# LS1C300B_176A_Msystem.net
KiCad netlist of a schematic drawn in Altium Designer
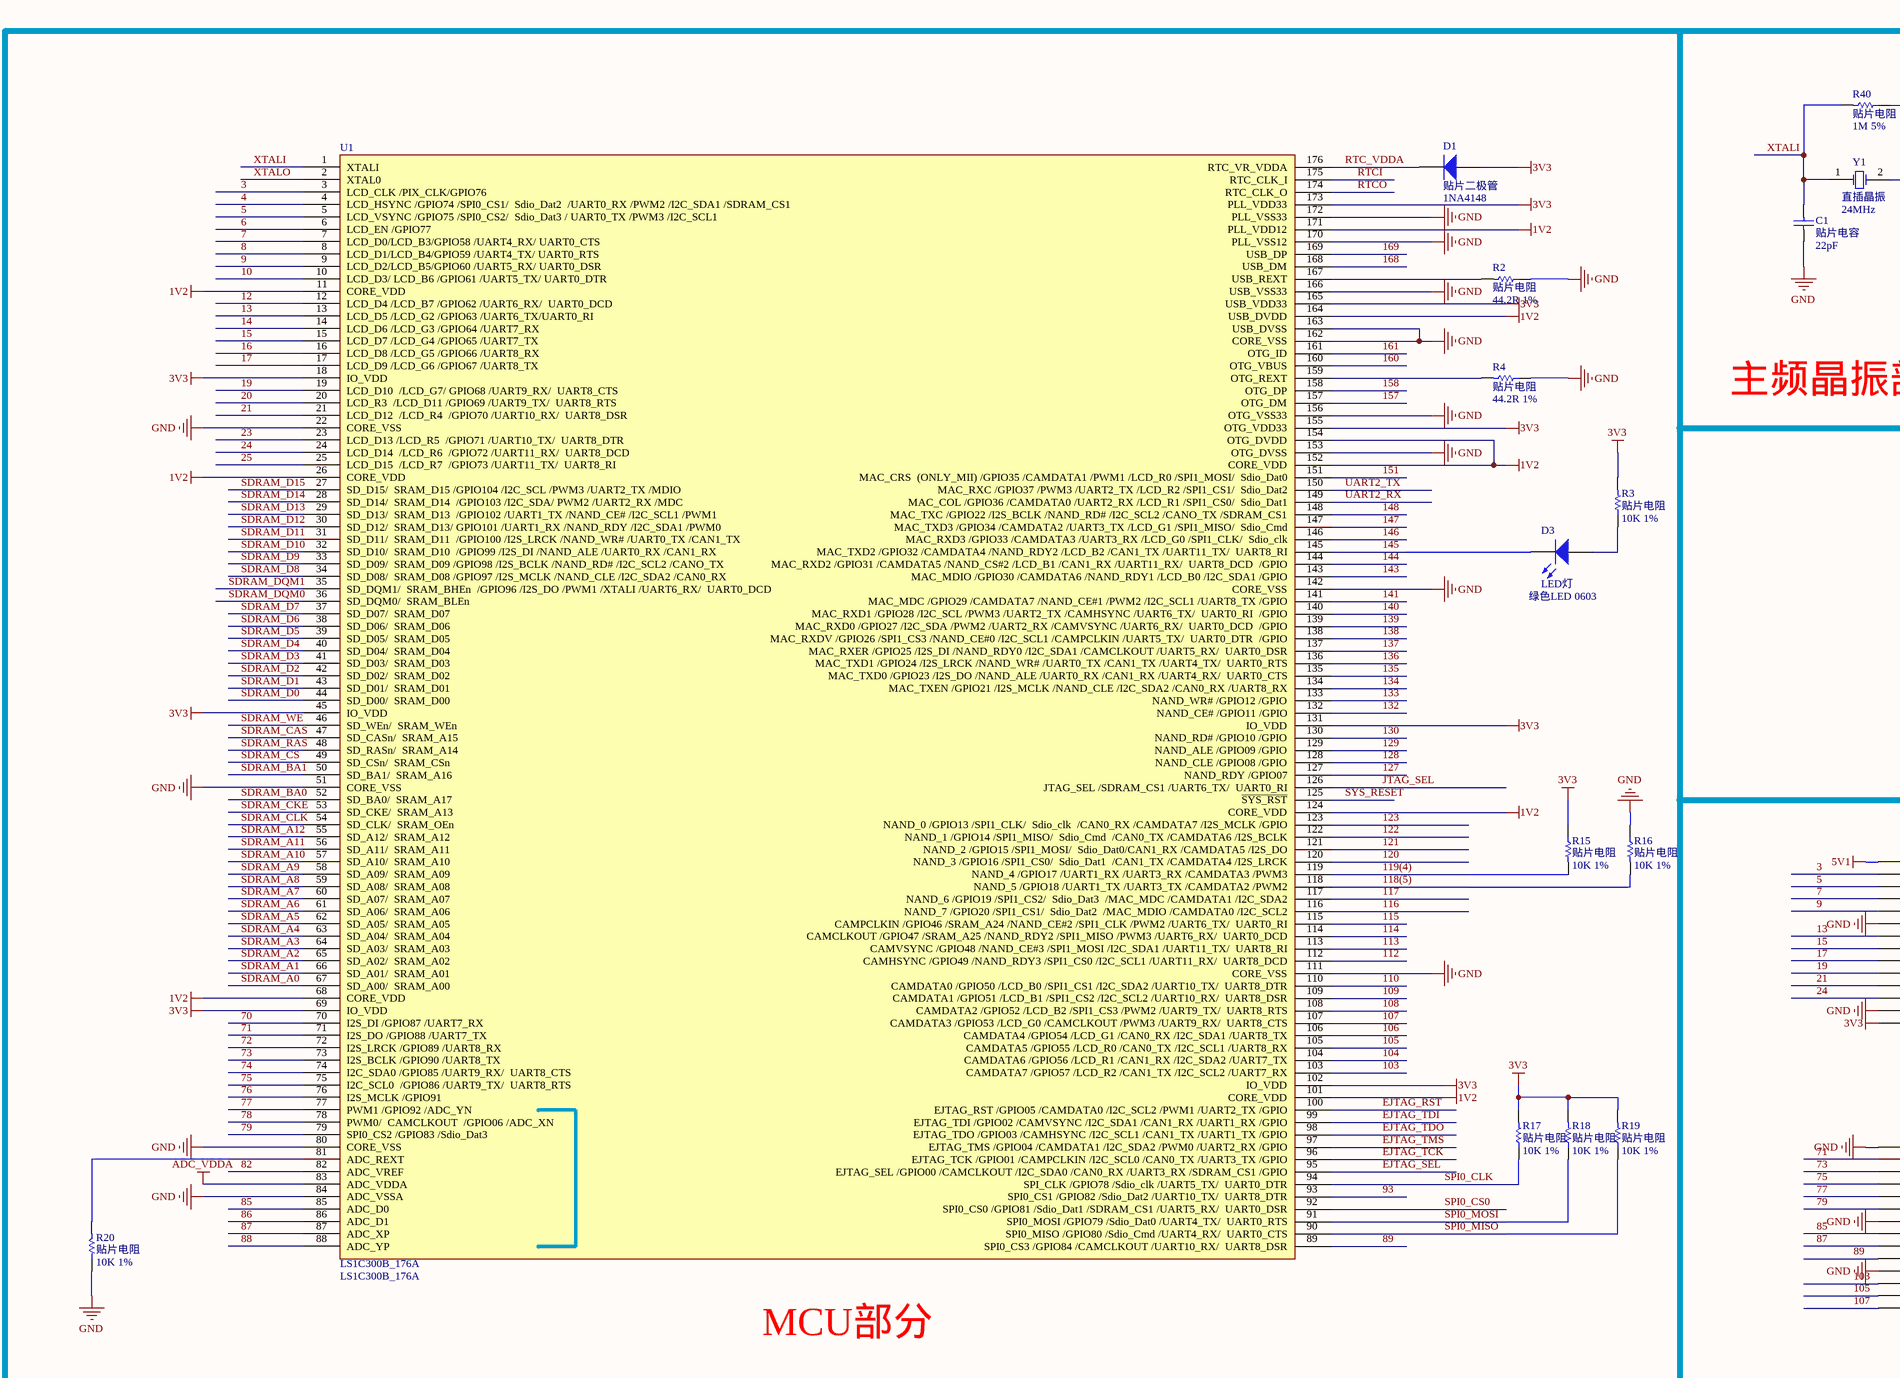
[diagram p0: LS1C300B_176A_Msystem.SchDoc, top left]
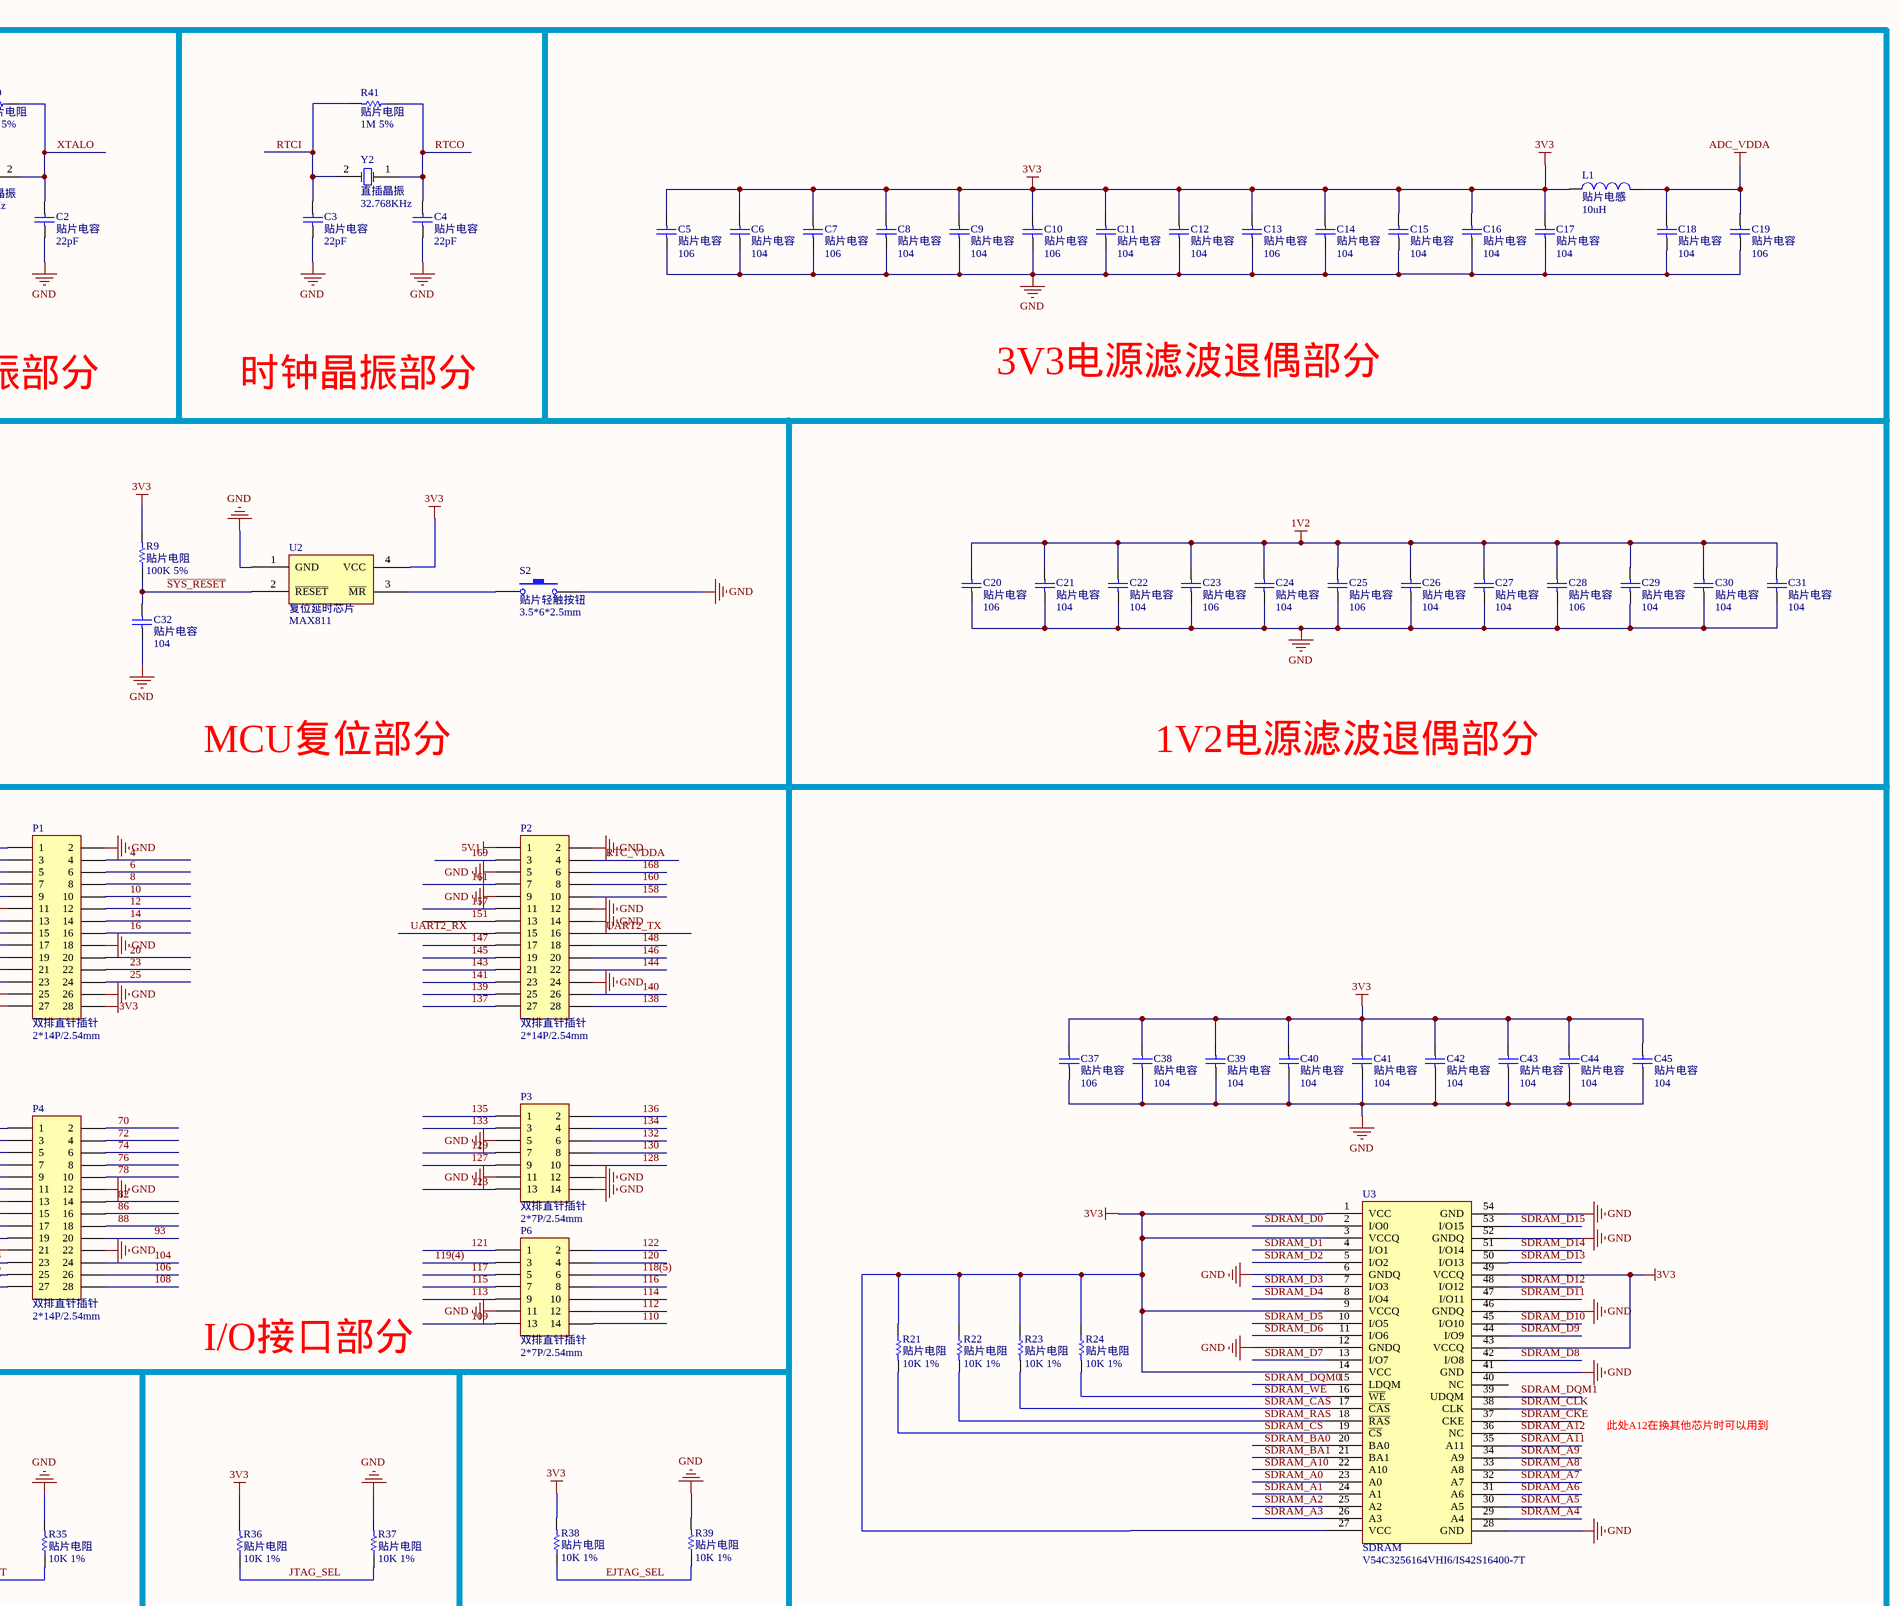
[diagram p1: LS1C300B_176A_Msystem.SchDoc, top right]
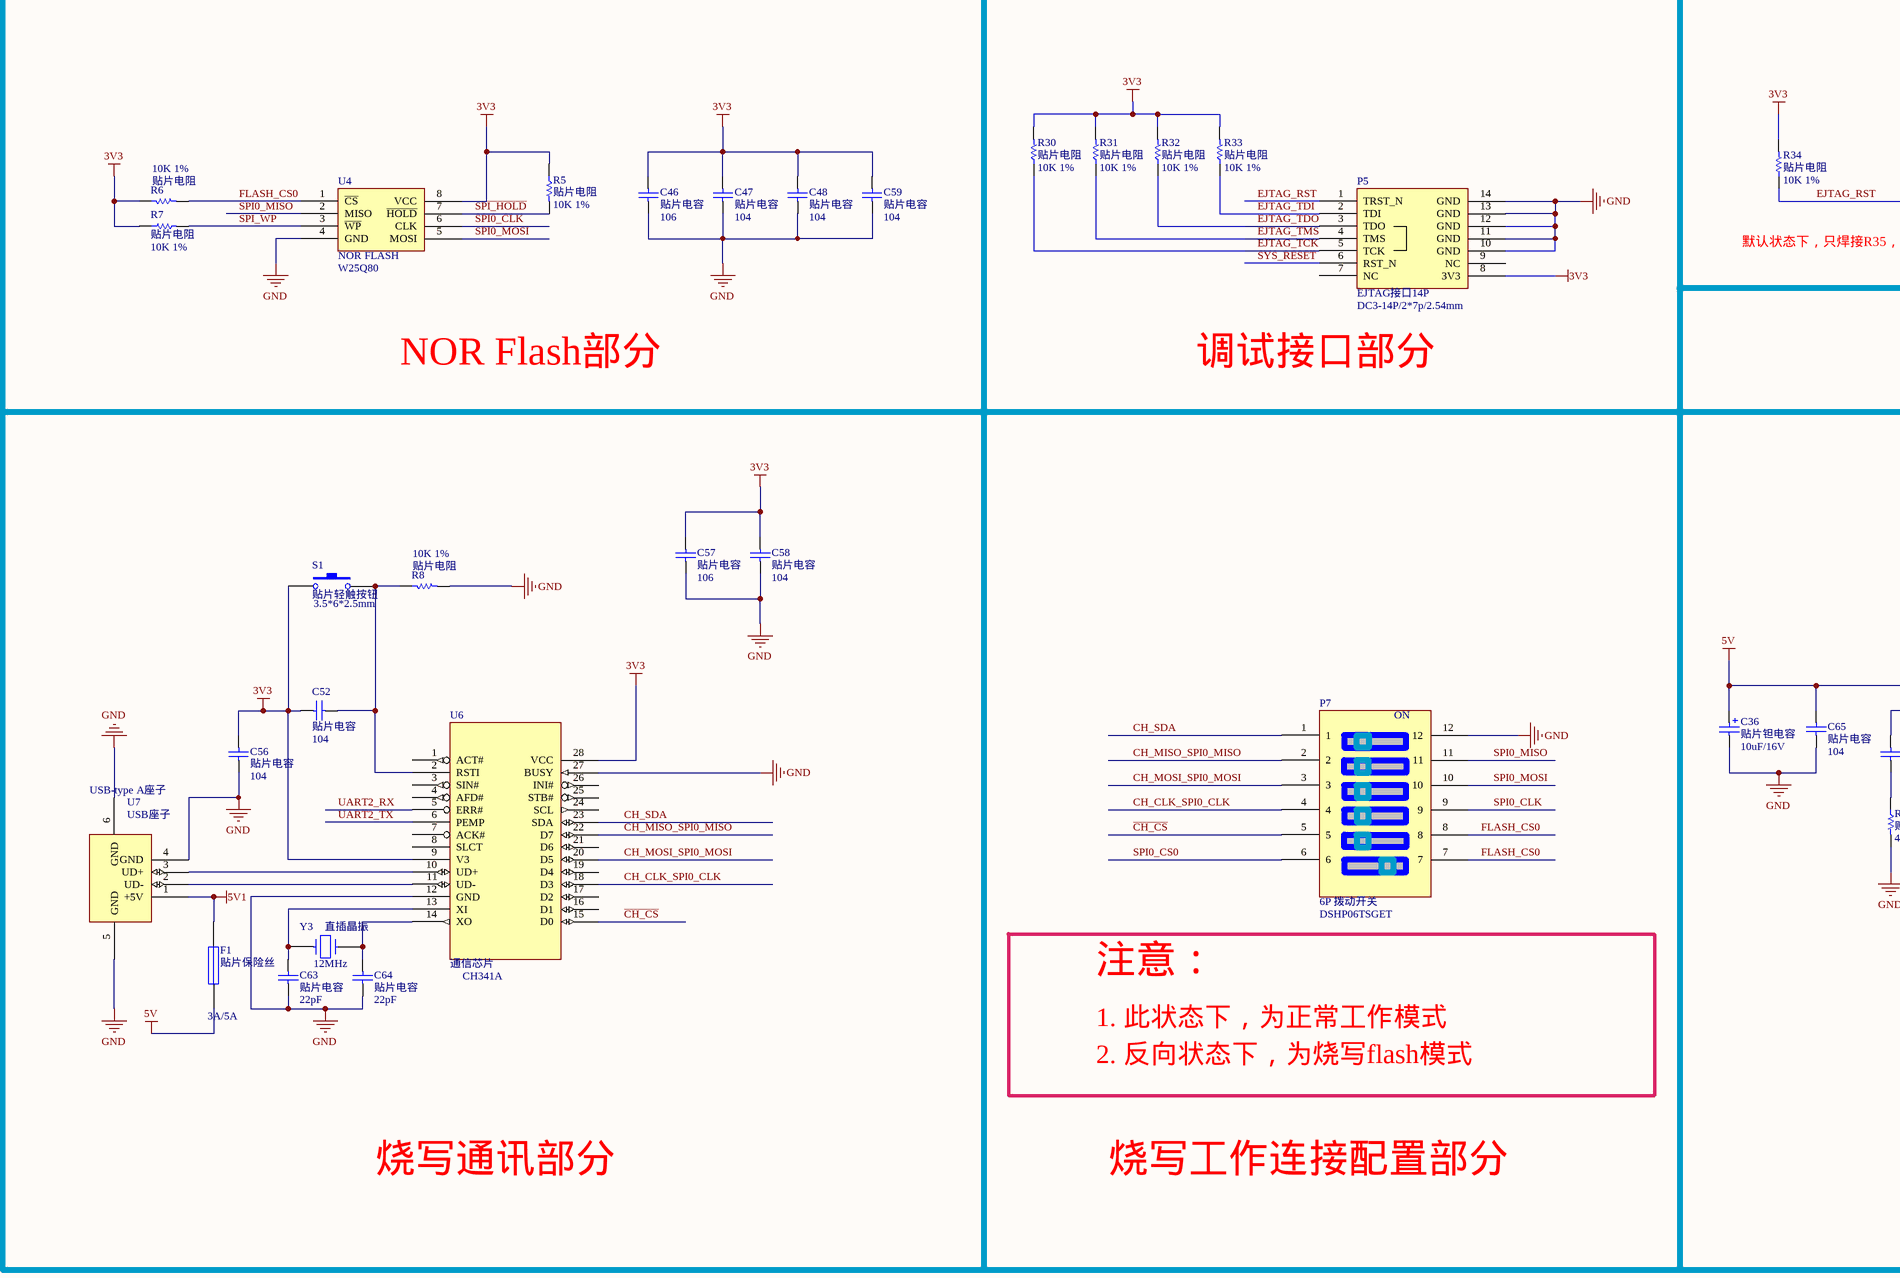
[diagram p2: LS1C300B_176A_Msystem.SchDoc, bottom left]
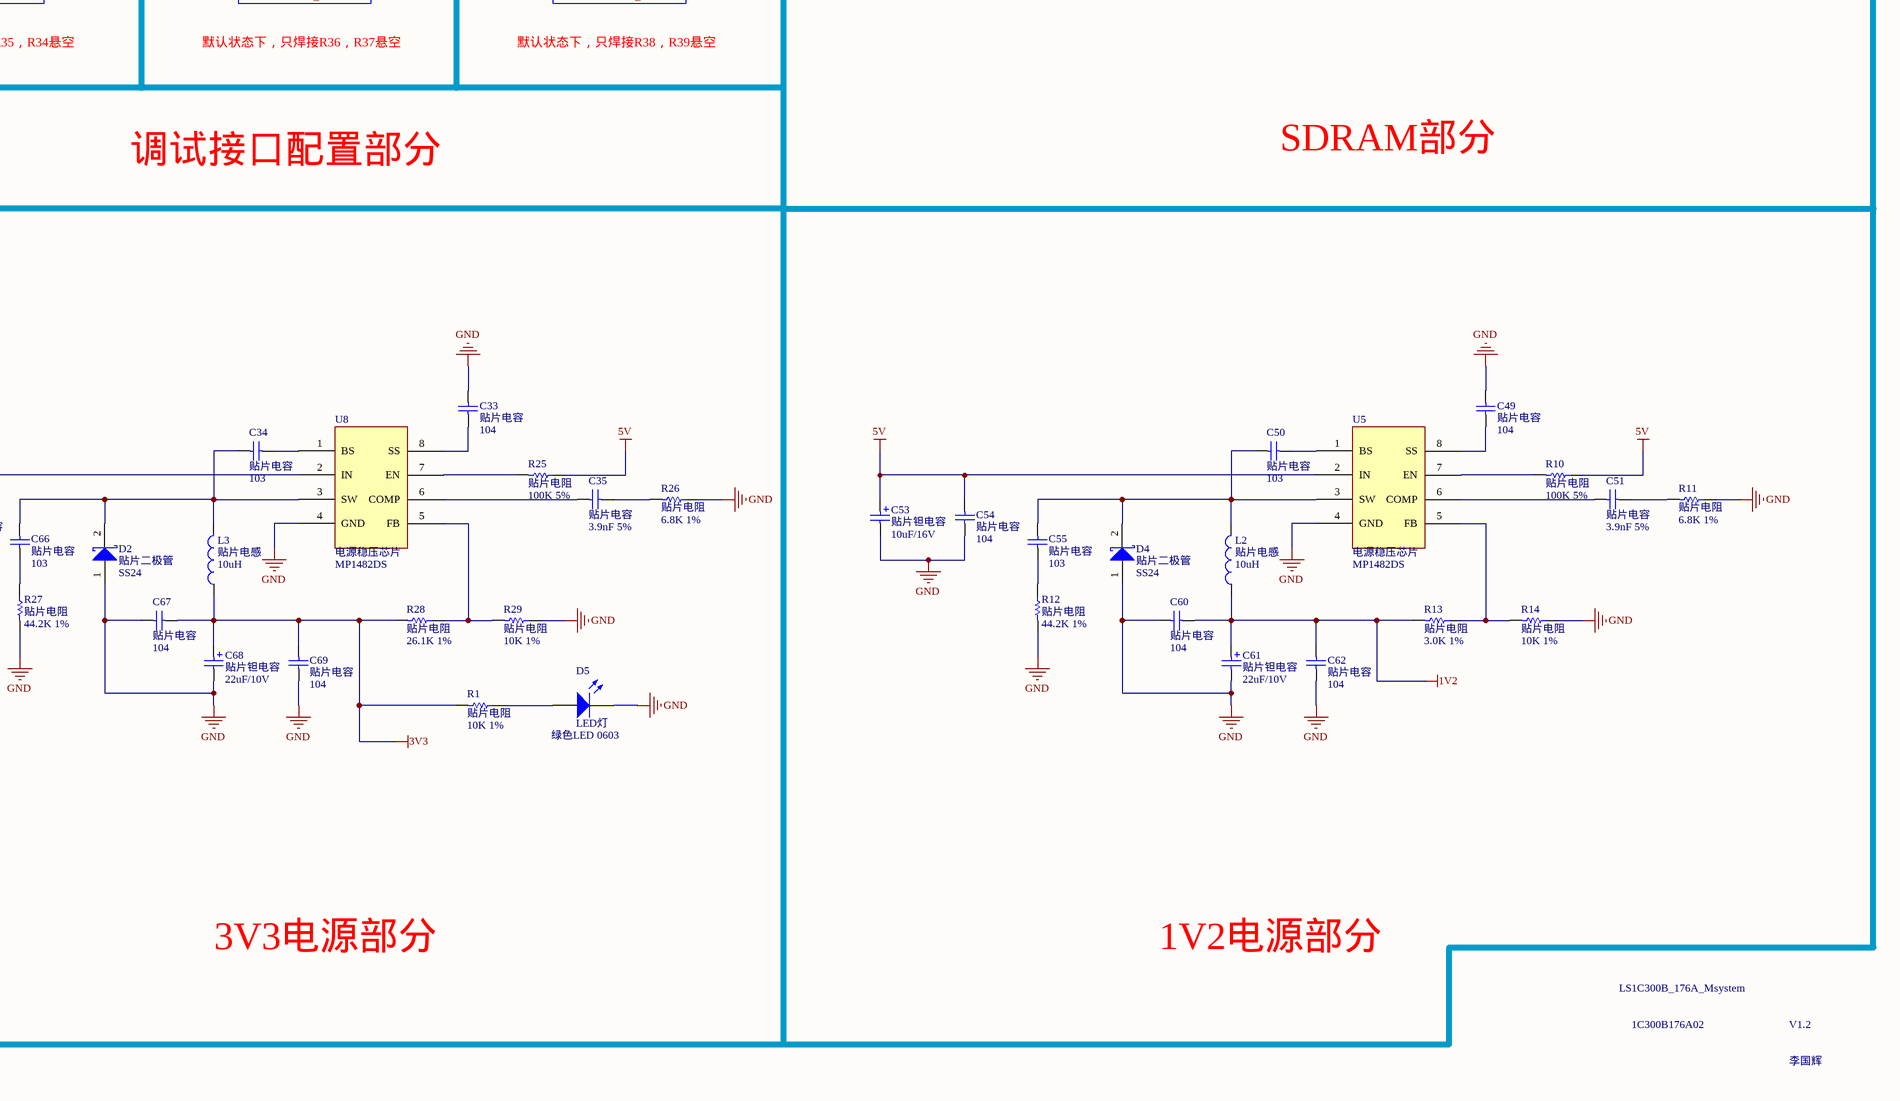
[diagram p3: LS1C300B_176A_Msystem.SchDoc, bottom right]

(export (version "E")
  (design (tool "Eeschema 10.0.6"))
  (components
    (comp (ref "C1")
      (value "贴片电容")
      (footprint "C0603")
      (description "Capacitor")
      (fields (field (name "ALTIUM_VALUE") "22pF") (field (name "PUBLISHER") "Altium Limited"))
      (libsource (lib "Miscellaneous Devices") (part "Cap"))
    )
    (comp (ref "C2")
      (value "贴片电容")
      (footprint "C0603")
      (description "Capacitor")
      (fields (field (name "ALTIUM_VALUE") "22pF") (field (name "PUBLISHER") "Altium Limited"))
      (libsource (lib "Miscellaneous Devices") (part "Cap"))
    )
    (comp (ref "C3")
      (value "贴片电容")
      (footprint "C0603")
      (description "Capacitor")
      (fields (field (name "ALTIUM_VALUE") "22pF") (field (name "PUBLISHER") "Altium Limited"))
      (libsource (lib "Miscellaneous Devices") (part "Cap"))
    )
    (comp (ref "C4")
      (value "贴片电容")
      (footprint "C0603")
      (description "Capacitor")
      (fields (field (name "ALTIUM_VALUE") "22pF") (field (name "PUBLISHER") "Altium Limited"))
      (libsource (lib "Miscellaneous Devices") (part "Cap"))
    )
    (comp (ref "C5")
      (value "贴片电容")
      (footprint "C0603")
      (description "Capacitor")
      (fields (field (name "ALTIUM_VALUE") "106") (field (name "PUBLISHER") "Altium Limited"))
      (libsource (lib "Miscellaneous Devices") (part "Cap"))
    )
    (comp (ref "C6")
      (value "贴片电容")
      (footprint "C0603")
      (description "Capacitor")
      (fields (field (name "ALTIUM_VALUE") "104") (field (name "PUBLISHER") "Altium Limited"))
      (libsource (lib "Miscellaneous Devices") (part "Cap"))
    )
    (comp (ref "C7")
      (value "贴片电容")
      (footprint "C0603")
      (description "Capacitor")
      (fields (field (name "ALTIUM_VALUE") "106") (field (name "PUBLISHER") "Altium Limited"))
      (libsource (lib "Miscellaneous Devices") (part "Cap"))
    )
    (comp (ref "C8")
      (value "贴片电容")
      (footprint "C0603")
      (description "Capacitor")
      (fields (field (name "ALTIUM_VALUE") "104") (field (name "PUBLISHER") "Altium Limited"))
      (libsource (lib "Miscellaneous Devices") (part "Cap"))
    )
    (comp (ref "C9")
      (value "贴片电容")
      (footprint "C0603")
      (description "Capacitor")
      (fields (field (name "ALTIUM_VALUE") "104") (field (name "PUBLISHER") "Altium Limited"))
      (libsource (lib "Miscellaneous Devices") (part "Cap"))
    )
    (comp (ref "C10")
      (value "贴片电容")
      (footprint "C0603")
      (description "Capacitor")
      (fields (field (name "ALTIUM_VALUE") "106") (field (name "PUBLISHER") "Altium Limited"))
      (libsource (lib "Miscellaneous Devices") (part "Cap"))
    )
    (comp (ref "C11")
      (value "贴片电容")
      (footprint "C0603")
      (description "Capacitor")
      (fields (field (name "ALTIUM_VALUE") "104") (field (name "PUBLISHER") "Altium Limited"))
      (libsource (lib "Miscellaneous Devices") (part "Cap"))
    )
    (comp (ref "C12")
      (value "贴片电容")
      (footprint "C0603")
      (description "Capacitor")
      (fields (field (name "ALTIUM_VALUE") "104") (field (name "PUBLISHER") "Altium Limited"))
      (libsource (lib "Miscellaneous Devices") (part "Cap"))
    )
    (comp (ref "C13")
      (value "贴片电容")
      (footprint "C0603")
      (description "Capacitor")
      (fields (field (name "ALTIUM_VALUE") "106") (field (name "PUBLISHER") "Altium Limited"))
      (libsource (lib "Miscellaneous Devices") (part "Cap"))
    )
    (comp (ref "C14")
      (value "贴片电容")
      (footprint "C0603")
      (description "Capacitor")
      (fields (field (name "ALTIUM_VALUE") "104") (field (name "PUBLISHER") "Altium Limited"))
      (libsource (lib "Miscellaneous Devices") (part "Cap"))
    )
    (comp (ref "C15")
      (value "贴片电容")
      (footprint "C0603")
      (description "Capacitor")
      (fields (field (name "ALTIUM_VALUE") "104") (field (name "PUBLISHER") "Altium Limited"))
      (libsource (lib "Miscellaneous Devices") (part "Cap"))
    )
    (comp (ref "C16")
      (value "贴片电容")
      (footprint "C0603")
      (description "Capacitor")
      (fields (field (name "ALTIUM_VALUE") "104") (field (name "PUBLISHER") "Altium Limited"))
      (libsource (lib "Miscellaneous Devices") (part "Cap"))
    )
    (comp (ref "C17")
      (value "贴片电容")
      (footprint "C0603")
      (description "Capacitor")
      (fields (field (name "ALTIUM_VALUE") "104") (field (name "PUBLISHER") "Altium Limited"))
      (libsource (lib "Miscellaneous Devices") (part "Cap"))
    )
    (comp (ref "C18")
      (value "贴片电容")
      (footprint "C0603")
      (description "Capacitor")
      (fields (field (name "ALTIUM_VALUE") "104") (field (name "PUBLISHER") "Altium Limited"))
      (libsource (lib "Miscellaneous Devices") (part "Cap"))
    )
    (comp (ref "C19")
      (value "贴片电容")
      (footprint "C0603")
      (description "Capacitor")
      (fields (field (name "ALTIUM_VALUE") "106") (field (name "PUBLISHER") "Altium Limited"))
      (libsource (lib "Miscellaneous Devices") (part "Cap"))
    )
    (comp (ref "C20")
      (value "贴片电容")
      (footprint "C0603")
      (description "Capacitor")
      (fields (field (name "ALTIUM_VALUE") "106") (field (name "PUBLISHER") "Altium Limited"))
      (libsource (lib "Miscellaneous Devices") (part "Cap"))
    )
    (comp (ref "C21")
      (value "贴片电容")
      (footprint "C0603")
      (description "Capacitor")
      (fields (field (name "ALTIUM_VALUE") "104") (field (name "PUBLISHER") "Altium Limited"))
      (libsource (lib "Miscellaneous Devices") (part "Cap"))
    )
    (comp (ref "C22")
      (value "贴片电容")
      (footprint "C0603")
      (description "Capacitor")
      (fields (field (name "ALTIUM_VALUE") "104") (field (name "PUBLISHER") "Altium Limited"))
      (libsource (lib "Miscellaneous Devices") (part "Cap"))
    )
    (comp (ref "C23")
      (value "贴片电容")
      (footprint "C0603")
      (description "Capacitor")
      (fields (field (name "ALTIUM_VALUE") "106") (field (name "PUBLISHER") "Altium Limited"))
      (libsource (lib "Miscellaneous Devices") (part "Cap"))
    )
    (comp (ref "C24")
      (value "贴片电容")
      (footprint "C0603")
      (description "Capacitor")
      (fields (field (name "ALTIUM_VALUE") "104") (field (name "PUBLISHER") "Altium Limited"))
      (libsource (lib "Miscellaneous Devices") (part "Cap"))
    )
    (comp (ref "C25")
      (value "贴片电容")
      (footprint "C0603")
      (description "Capacitor")
      (fields (field (name "ALTIUM_VALUE") "106") (field (name "PUBLISHER") "Altium Limited"))
      (libsource (lib "Miscellaneous Devices") (part "Cap"))
    )
    (comp (ref "C26")
      (value "贴片电容")
      (footprint "C0603")
      (description "Capacitor")
      (fields (field (name "ALTIUM_VALUE") "104") (field (name "PUBLISHER") "Altium Limited"))
      (libsource (lib "Miscellaneous Devices") (part "Cap"))
    )
    (comp (ref "C27")
      (value "贴片电容")
      (footprint "C0603")
      (description "Capacitor")
      (fields (field (name "ALTIUM_VALUE") "104") (field (name "PUBLISHER") "Altium Limited"))
      (libsource (lib "Miscellaneous Devices") (part "Cap"))
    )
    (comp (ref "C28")
      (value "贴片电容")
      (footprint "C0603")
      (description "Capacitor")
      (fields (field (name "ALTIUM_VALUE") "106") (field (name "PUBLISHER") "Altium Limited"))
      (libsource (lib "Miscellaneous Devices") (part "Cap"))
    )
    (comp (ref "C29")
      (value "贴片电容")
      (footprint "C0603")
      (description "Capacitor")
      (fields (field (name "ALTIUM_VALUE") "104") (field (name "PUBLISHER") "Altium Limited"))
      (libsource (lib "Miscellaneous Devices") (part "Cap"))
    )
    (comp (ref "C30")
      (value "贴片电容")
      (footprint "C0603")
      (description "Capacitor")
      (fields (field (name "ALTIUM_VALUE") "104") (field (name "PUBLISHER") "Altium Limited"))
      (libsource (lib "Miscellaneous Devices") (part "Cap"))
    )
    (comp (ref "C31")
      (value "贴片电容")
      (footprint "C0603")
      (description "Capacitor")
      (fields (field (name "ALTIUM_VALUE") "104") (field (name "PUBLISHER") "Altium Limited"))
      (libsource (lib "Miscellaneous Devices") (part "Cap"))
    )
    (comp (ref "C32")
      (value "贴片电容")
      (footprint "C0603")
      (description "Capacitor")
      (fields (field (name "ALTIUM_VALUE") "104") (field (name "PUBLISHER") "Altium Limited"))
      (libsource (lib "Miscellaneous Devices") (part "Cap"))
    )
    (comp (ref "C33")
      (value "贴片电容")
      (footprint "C0603")
      (description "Capacitor")
      (fields (field (name "ALTIUM_VALUE") "104") (field (name "PUBLISHER") "Altium Limited"))
      (libsource (lib "Miscellaneous Devices") (part "Cap"))
    )
    (comp (ref "C34")
      (value "贴片电容")
      (footprint "C0603")
      (description "Capacitor")
      (fields (field (name "ALTIUM_VALUE") "103") (field (name "PUBLISHER") "Altium Limited"))
      (libsource (lib "Miscellaneous Devices") (part "Cap"))
    )
    (comp (ref "C35")
      (value "贴片电容")
      (footprint "C0603")
      (description "Capacitor")
      (fields (field (name "ALTIUM_VALUE") "3.9nF 5%") (field (name "PUBLISHER") "Altium Limited"))
      (libsource (lib "Miscellaneous Devices") (part "Cap"))
    )
    (comp (ref "C36")
      (value "贴片钽电容")
      (footprint "P-C1206")
      (description "Polarized Capacitor (Axial)")
      (fields (field (name "ALTIUM_VALUE") "10uF/16V") (field (name "PUBLISHER") "Altium Limited"))
      (libsource (lib "Miscellaneous Devices") (part "Cap Pol2"))
    )
    (comp (ref "C37")
      (value "贴片电容")
      (footprint "C0603")
      (description "Capacitor")
      (fields (field (name "ALTIUM_VALUE") "106") (field (name "PUBLISHER") "Altium Limited"))
      (libsource (lib "Miscellaneous Devices") (part "Cap"))
    )
    (comp (ref "C38")
      (value "贴片电容")
      (footprint "C0603")
      (description "Capacitor")
      (fields (field (name "ALTIUM_VALUE") "104") (field (name "PUBLISHER") "Altium Limited"))
      (libsource (lib "Miscellaneous Devices") (part "Cap"))
    )
    (comp (ref "C39")
      (value "贴片电容")
      (footprint "C0603")
      (description "Capacitor")
      (fields (field (name "ALTIUM_VALUE") "104") (field (name "PUBLISHER") "Altium Limited"))
      (libsource (lib "Miscellaneous Devices") (part "Cap"))
    )
    (comp (ref "C40")
      (value "贴片电容")
      (footprint "C0603")
      (description "Capacitor")
      (fields (field (name "ALTIUM_VALUE") "104") (field (name "PUBLISHER") "Altium Limited"))
      (libsource (lib "Miscellaneous Devices") (part "Cap"))
    )
    (comp (ref "C41")
      (value "贴片电容")
      (footprint "C0603")
      (description "Capacitor")
      (fields (field (name "ALTIUM_VALUE") "104") (field (name "PUBLISHER") "Altium Limited"))
      (libsource (lib "Miscellaneous Devices") (part "Cap"))
    )
    (comp (ref "C42")
      (value "贴片电容")
      (footprint "C0603")
      (description "Capacitor")
      (fields (field (name "ALTIUM_VALUE") "104") (field (name "PUBLISHER") "Altium Limited"))
      (libsource (lib "Miscellaneous Devices") (part "Cap"))
    )
    (comp (ref "C43")
      (value "贴片电容")
      (footprint "C0603")
      (description "Capacitor")
      (fields (field (name "ALTIUM_VALUE") "104") (field (name "PUBLISHER") "Altium Limited"))
      (libsource (lib "Miscellaneous Devices") (part "Cap"))
    )
    (comp (ref "C44")
      (value "贴片电容")
      (footprint "C0603")
      (description "Capacitor")
      (fields (field (name "ALTIUM_VALUE") "104") (field (name "PUBLISHER") "Altium Limited"))
      (libsource (lib "Miscellaneous Devices") (part "Cap"))
    )
    (comp (ref "C45")
      (value "贴片电容")
      (footprint "C0603")
      (description "Capacitor")
      (fields (field (name "ALTIUM_VALUE") "104") (field (name "PUBLISHER") "Altium Limited"))
      (libsource (lib "Miscellaneous Devices") (part "Cap"))
    )
    (comp (ref "C46")
      (value "贴片电容")
      (footprint "C0603")
      (description "Capacitor")
      (fields (field (name "ALTIUM_VALUE") "106") (field (name "PUBLISHER") "Altium Limited"))
      (libsource (lib "Miscellaneous Devices") (part "Cap"))
    )
    (comp (ref "C47")
      (value "贴片电容")
      (footprint "C0603")
      (description "Capacitor")
      (fields (field (name "ALTIUM_VALUE") "104") (field (name "PUBLISHER") "Altium Limited"))
      (libsource (lib "Miscellaneous Devices") (part "Cap"))
    )
    (comp (ref "C48")
      (value "贴片电容")
      (footprint "C0603")
      (description "Capacitor")
      (fields (field (name "ALTIUM_VALUE") "104") (field (name "PUBLISHER") "Altium Limited"))
      (libsource (lib "Miscellaneous Devices") (part "Cap"))
    )
    (comp (ref "C49")
      (value "贴片电容")
      (footprint "C0603")
      (description "Capacitor")
      (fields (field (name "ALTIUM_VALUE") "104") (field (name "PUBLISHER") "Altium Limited"))
      (libsource (lib "Miscellaneous Devices") (part "Cap"))
    )
    (comp (ref "C50")
      (value "贴片电容")
      (footprint "C0603")
      (description "Capacitor")
      (fields (field (name "ALTIUM_VALUE") "103") (field (name "PUBLISHER") "Altium Limited"))
      (libsource (lib "Miscellaneous Devices") (part "Cap"))
    )
    (comp (ref "C51")
      (value "贴片电容")
      (footprint "C0603")
      (description "Capacitor")
      (fields (field (name "ALTIUM_VALUE") "3.9nF 5%") (field (name "PUBLISHER") "Altium Limited"))
      (libsource (lib "Miscellaneous Devices") (part "Cap"))
    )
    (comp (ref "C52")
      (value "贴片电容")
      (footprint "C0603")
      (description "Capacitor")
      (fields (field (name "ALTIUM_VALUE") "104") (field (name "PUBLISHER") "Altium Limited"))
      (libsource (lib "Miscellaneous Devices") (part "Cap"))
    )
    (comp (ref "C53")
      (value "贴片钽电容")
      (footprint "P-C1206")
      (description "Polarized Capacitor (Axial)")
      (fields (field (name "ALTIUM_VALUE") "10uF/16V") (field (name "PUBLISHER") "Altium Limited"))
      (libsource (lib "Miscellaneous Devices") (part "Cap Pol2"))
    )
    (comp (ref "C54")
      (value "贴片电容")
      (footprint "C0603")
      (description "Capacitor")
      (fields (field (name "ALTIUM_VALUE") "104") (field (name "PUBLISHER") "Altium Limited"))
      (libsource (lib "Miscellaneous Devices") (part "Cap"))
    )
    (comp (ref "C55")
      (value "贴片电容")
      (footprint "C0603")
      (description "Capacitor")
      (fields (field (name "ALTIUM_VALUE") "103") (field (name "PUBLISHER") "Altium Limited"))
      (libsource (lib "Miscellaneous Devices") (part "Cap"))
    )
    (comp (ref "C56")
      (value "贴片电容")
      (footprint "C0603")
      (description "Capacitor")
      (fields (field (name "ALTIUM_VALUE") "104") (field (name "PUBLISHER") "Altium Limited"))
      (libsource (lib "Miscellaneous Devices") (part "Cap"))
    )
    (comp (ref "C57")
      (value "贴片电容")
      (footprint "C0603")
      (description "Capacitor")
      (fields (field (name "ALTIUM_VALUE") "106") (field (name "PUBLISHER") "Altium Limited"))
      (libsource (lib "Miscellaneous Devices") (part "Cap"))
    )
    (comp (ref "C58")
      (value "贴片电容")
      (footprint "C0603")
      (description "Capacitor")
      (fields (field (name "ALTIUM_VALUE") "104") (field (name "PUBLISHER") "Altium Limited"))
      (libsource (lib "Miscellaneous Devices") (part "Cap"))
    )
    (comp (ref "C59")
      (value "贴片电容")
      (footprint "C0603")
      (description "Capacitor")
      (fields (field (name "ALTIUM_VALUE") "104") (field (name "PUBLISHER") "Altium Limited"))
      (libsource (lib "Miscellaneous Devices") (part "Cap"))
    )
    (comp (ref "C60")
      (value "贴片电容")
      (footprint "C0603")
      (description "Capacitor")
      (fields (field (name "ALTIUM_VALUE") "104") (field (name "PUBLISHER") "Altium Limited"))
      (libsource (lib "Miscellaneous Devices") (part "Cap"))
    )
    (comp (ref "C61")
      (value "贴片钽电容")
      (footprint "P-C1206")
      (description "Polarized Capacitor (Axial)")
      (fields (field (name "ALTIUM_VALUE") "22uF/10V") (field (name "PUBLISHER") "Altium Limited"))
      (libsource (lib "Miscellaneous Devices") (part "Cap Pol2"))
    )
    (comp (ref "C62")
      (value "贴片电容")
      (footprint "C0603")
      (description "Capacitor")
      (fields (field (name "ALTIUM_VALUE") "104") (field (name "PUBLISHER") "Altium Limited"))
      (libsource (lib "Miscellaneous Devices") (part "Cap"))
    )
    (comp (ref "C63")
      (value "贴片电容")
      (footprint "C0603")
      (description "Capacitor")
      (fields (field (name "ALTIUM_VALUE") "22pF") (field (name "PUBLISHER") "Altium Limited"))
      (libsource (lib "Miscellaneous Devices") (part "Cap"))
    )
    (comp (ref "C64")
      (value "贴片电容")
      (footprint "C0603")
      (description "Capacitor")
      (fields (field (name "ALTIUM_VALUE") "22pF") (field (name "PUBLISHER") "Altium Limited"))
      (libsource (lib "Miscellaneous Devices") (part "Cap"))
    )
    (comp (ref "C65")
      (value "贴片电容")
      (footprint "C0603")
      (description "Capacitor")
      (fields (field (name "ALTIUM_VALUE") "104") (field (name "PUBLISHER") "Altium Limited"))
      (libsource (lib "Miscellaneous Devices") (part "Cap"))
    )
    (comp (ref "C66")
      (value "贴片电容")
      (footprint "C0603")
      (description "Capacitor")
      (fields (field (name "ALTIUM_VALUE") "103") (field (name "PUBLISHER") "Altium Limited"))
      (libsource (lib "Miscellaneous Devices") (part "Cap"))
    )
    (comp (ref "C67")
      (value "贴片电容")
      (footprint "C0603")
      (description "Capacitor")
      (fields (field (name "ALTIUM_VALUE") "104") (field (name "PUBLISHER") "Altium Limited"))
      (libsource (lib "Miscellaneous Devices") (part "Cap"))
    )
    (comp (ref "C68")
      (value "贴片钽电容")
      (footprint "P-C1206")
      (description "Polarized Capacitor (Axial)")
      (fields (field (name "ALTIUM_VALUE") "22uF/10V") (field (name "PUBLISHER") "Altium Limited"))
      (libsource (lib "Miscellaneous Devices") (part "Cap Pol2"))
    )
    (comp (ref "C69")
      (value "贴片电容")
      (footprint "C0603")
      (description "Capacitor")
      (fields (field (name "ALTIUM_VALUE") "104") (field (name "PUBLISHER") "Altium Limited"))
      (libsource (lib "Miscellaneous Devices") (part "Cap"))
    )
    (comp (ref "D1")
      (value "贴片二极管")
      (footprint "LL-34")
      (description "Default Diode")
      (fields (field (name "ALTIUM_VALUE") "1NA4148") (field (name "PUBLISHER") "Altium Limited"))
      (libsource (lib "Miscellaneous Devices") (part "Diode"))
    )
    (comp (ref "D2")
      (value "贴片二极管")
      (footprint "DO-214AC")
      (fields (field (name "ALTIUM_VALUE") "SS24"))
      (libsource (lib "LGHLIB") (part "1N47xx"))
    )
    (comp (ref "D3")
      (value "LED灯")
      (footprint "LED-0603")
      (description "Typical INFRARED GaAs LED")
      (fields (field (name "ALTIUM_VALUE") "绿色LED 0603") (field (name "PUBLISHER") "Altium Limited"))
      (libsource (lib "Miscellaneous Devices") (part "LED0"))
    )
    (comp (ref "D4")
      (value "贴片二极管")
      (footprint "DO-214AC")
      (fields (field (name "ALTIUM_VALUE") "SS24"))
      (libsource (lib "LGHLIB") (part "1N47xx"))
    )
    (comp (ref "D5")
      (value "LED灯")
      (footprint "LED-0603")
      (description "Typical INFRARED GaAs LED")
      (fields (field (name "ALTIUM_VALUE") "绿色LED 0603") (field (name "PUBLISHER") "Altium Limited"))
      (libsource (lib "Miscellaneous Devices") (part "LED0"))
    )
    (comp (ref "F1")
      (value "贴片保险丝")
      (footprint "R1206")
      (description "Fuse")
      (fields (field (name "ALTIUM_VALUE") "3A/5A") (field (name "PUBLISHER") "Altium Limited"))
      (libsource (lib "Miscellaneous Devices") (part "Fuse 1"))
    )
    (comp (ref "L1")
      (value "贴片电感")
      (footprint "L0603")
      (description "Inductor")
      (fields (field (name "ALTIUM_VALUE") "10uH") (field (name "PUBLISHER") "Altium Limited"))
      (libsource (lib "Miscellaneous Devices") (part "Inductor"))
    )
    (comp (ref "L2")
      (value "贴片电感")
      (footprint "L0603")
      (description "Inductor")
      (fields (field (name "ALTIUM_VALUE") "10uH") (field (name "PUBLISHER") "Altium Limited"))
      (libsource (lib "Miscellaneous Devices") (part "Inductor"))
    )
    (comp (ref "L3")
      (value "贴片电感")
      (footprint "L0603")
      (description "Inductor")
      (fields (field (name "ALTIUM_VALUE") "10uH") (field (name "PUBLISHER") "Altium Limited"))
      (libsource (lib "Miscellaneous Devices") (part "Inductor"))
    )
    (comp (ref "P1")
      (value "双排直针插针")
      (footprint "HDR2X14")
      (description "Header, 14-Pin, Dual row")
      (fields (field (name "ALTIUM_VALUE") "2*14P/2.54mm") (field (name "PUBLISHER") "Altium Limited"))
      (libsource (lib "Miscellaneous Connectors") (part "MHDR2X14"))
    )
    (comp (ref "P2")
      (value "双排直针插针")
      (footprint "HDR2X14")
      (description "Header, 14-Pin, Dual row")
      (fields (field (name "ALTIUM_VALUE") "2*14P/2.54mm") (field (name "PUBLISHER") "Altium Limited"))
      (libsource (lib "Miscellaneous Connectors") (part "MHDR2X14"))
    )
    (comp (ref "P3")
      (value "双排直针插针")
      (footprint "HDR2X7")
      (description "Header, 7-Pin, Dual row")
      (fields (field (name "ALTIUM_VALUE") "2*7P/2.54mm") (field (name "PUBLISHER") "Altium Limited"))
      (libsource (lib "Miscellaneous Connectors") (part "MHDR2X7"))
    )
    (comp (ref "P4")
      (value "双排直针插针")
      (footprint "HDR2X14")
      (description "Header, 14-Pin, Dual row")
      (fields (field (name "ALTIUM_VALUE") "2*14P/2.54mm") (field (name "PUBLISHER") "Altium Limited"))
      (libsource (lib "Miscellaneous Connectors") (part "MHDR2X14"))
    )
    (comp (ref "P5")
      (value "EJTAG接口14P")
      (footprint "DC3-14P")
      (fields (field (name "ALTIUM_VALUE") "DC3-14P/2*7p/2.54mm"))
      (libsource (lib "LGHLIB") (part "EJTAG-14P"))
    )
    (comp (ref "P6")
      (value "双排直针插针")
      (footprint "HDR2X7")
      (description "Header, 7-Pin, Dual row")
      (fields (field (name "ALTIUM_VALUE") "2*7P/2.54mm") (field (name "PUBLISHER") "Altium Limited"))
      (libsource (lib "Miscellaneous Connectors") (part "MHDR2X7"))
    )
    (comp (ref "P7")
      (value "6P 拨动开关")
      (footprint "DSHP06")
      (description "台湾KE 公司  DSHP06TSGET")
      (fields (field (name "ALTIUM_VALUE") "DSHP06TSGET"))
      (libsource (lib "LGHLIB") (part "DSHP06TSGET"))
    )
    (comp (ref "R1")
      (value "贴片电阻")
      (footprint "R0603")
      (description "Resistor")
      (fields (field (name "ALTIUM_VALUE") "10K 1%") (field (name "PUBLISHER") "Altium Limited"))
      (libsource (lib "Miscellaneous Devices") (part "Res1"))
    )
    (comp (ref "R2")
      (value "贴片电阻")
      (footprint "R0603")
      (description "Resistor")
      (fields (field (name "ALTIUM_VALUE") "44.2R 1%") (field (name "PUBLISHER") "Altium Limited"))
      (libsource (lib "Miscellaneous Devices") (part "Res1"))
    )
    (comp (ref "R3")
      (value "贴片电阻")
      (footprint "R0603")
      (description "Resistor")
      (fields (field (name "ALTIUM_VALUE") "10K 1%") (field (name "PUBLISHER") "Altium Limited"))
      (libsource (lib "Miscellaneous Devices") (part "Res1"))
    )
    (comp (ref "R4")
      (value "贴片电阻")
      (footprint "R0603")
      (description "Resistor")
      (fields (field (name "ALTIUM_VALUE") "44.2R 1%") (field (name "PUBLISHER") "Altium Limited"))
      (libsource (lib "Miscellaneous Devices") (part "Res1"))
    )
    (comp (ref "R5")
      (value "贴片电阻")
      (footprint "R0603")
      (description "Resistor")
      (fields (field (name "ALTIUM_VALUE") "10K 1%") (field (name "PUBLISHER") "Altium Limited"))
      (libsource (lib "Miscellaneous Devices") (part "Res1"))
    )
    (comp (ref "R6")
      (value "贴片电阻")
      (footprint "R0603")
      (description "Resistor")
      (fields (field (name "ALTIUM_VALUE") "10K 1%") (field (name "PUBLISHER") "Altium Limited"))
      (libsource (lib "Miscellaneous Devices") (part "Res1"))
    )
    (comp (ref "R7")
      (value "贴片电阻")
      (footprint "R0603")
      (description "Resistor")
      (fields (field (name "ALTIUM_VALUE") "10K 1%") (field (name "PUBLISHER") "Altium Limited"))
      (libsource (lib "Miscellaneous Devices") (part "Res1"))
    )
    (comp (ref "R8")
      (value "贴片电阻")
      (footprint "R0603")
      (description "Resistor")
      (fields (field (name "ALTIUM_VALUE") "10K 1%") (field (name "PUBLISHER") "Altium Limited"))
      (libsource (lib "Miscellaneous Devices") (part "Res1"))
    )
    (comp (ref "R9")
      (value "贴片电阻")
      (footprint "R0603")
      (description "Resistor")
      (fields (field (name "ALTIUM_VALUE") "100K 5%") (field (name "PUBLISHER") "Altium Limited"))
      (libsource (lib "Miscellaneous Devices") (part "Res1"))
    )
    (comp (ref "R10")
      (value "贴片电阻")
      (footprint "R0603")
      (description "Resistor")
      (fields (field (name "ALTIUM_VALUE") "100K 5%") (field (name "PUBLISHER") "Altium Limited"))
      (libsource (lib "Miscellaneous Devices") (part "Res1"))
    )
    (comp (ref "R11")
      (value "贴片电阻")
      (footprint "R0603")
      (description "Resistor")
      (fields (field (name "ALTIUM_VALUE") "6.8K 1%") (field (name "PUBLISHER") "Altium Limited"))
      (libsource (lib "Miscellaneous Devices") (part "Res1"))
    )
    (comp (ref "R12")
      (value "贴片电阻")
      (footprint "R0603")
      (description "Resistor")
      (fields (field (name "ALTIUM_VALUE") "44.2K 1%") (field (name "PUBLISHER") "Altium Limited"))
      (libsource (lib "Miscellaneous Devices") (part "Res1"))
    )
    (comp (ref "R13")
      (value "贴片电阻")
      (footprint "R0603")
      (description "Resistor")
      (fields (field (name "ALTIUM_VALUE") "3.0K 1%") (field (name "PUBLISHER") "Altium Limited"))
      (libsource (lib "Miscellaneous Devices") (part "Res1"))
    )
    (comp (ref "R14")
      (value "贴片电阻")
      (footprint "R0603")
      (description "Resistor")
      (fields (field (name "ALTIUM_VALUE") "10K 1%") (field (name "PUBLISHER") "Altium Limited"))
      (libsource (lib "Miscellaneous Devices") (part "Res1"))
    )
    (comp (ref "R15")
      (value "贴片电阻")
      (footprint "R0603")
      (description "Resistor")
      (fields (field (name "ALTIUM_VALUE") "10K 1%") (field (name "PUBLISHER") "Altium Limited"))
      (libsource (lib "Miscellaneous Devices") (part "Res1"))
    )
    (comp (ref "R16")
      (value "贴片电阻")
      (footprint "R0603")
      (description "Resistor")
      (fields (field (name "ALTIUM_VALUE") "10K 1%") (field (name "PUBLISHER") "Altium Limited"))
      (libsource (lib "Miscellaneous Devices") (part "Res1"))
    )
    (comp (ref "R17")
      (value "贴片电阻")
      (footprint "R0603")
      (description "Resistor")
      (fields (field (name "ALTIUM_VALUE") "10K 1%") (field (name "PUBLISHER") "Altium Limited"))
      (libsource (lib "Miscellaneous Devices") (part "Res1"))
    )
    (comp (ref "R18")
      (value "贴片电阻")
      (footprint "R0603")
      (description "Resistor")
      (fields (field (name "ALTIUM_VALUE") "10K 1%") (field (name "PUBLISHER") "Altium Limited"))
      (libsource (lib "Miscellaneous Devices") (part "Res1"))
    )
    (comp (ref "R19")
      (value "贴片电阻")
      (footprint "R0603")
      (description "Resistor")
      (fields (field (name "ALTIUM_VALUE") "10K 1%") (field (name "PUBLISHER") "Altium Limited"))
      (libsource (lib "Miscellaneous Devices") (part "Res1"))
    )
    (comp (ref "R20")
      (value "贴片电阻")
      (footprint "R0603")
      (description "Resistor")
      (fields (field (name "ALTIUM_VALUE") "10K 1%") (field (name "PUBLISHER") "Altium Limited"))
      (libsource (lib "Miscellaneous Devices") (part "Res1"))
    )
    (comp (ref "R21")
      (value "贴片电阻")
      (footprint "R0603")
      (description "Resistor")
      (fields (field (name "ALTIUM_VALUE") "10K 1%") (field (name "PUBLISHER") "Altium Limited"))
      (libsource (lib "Miscellaneous Devices") (part "Res1"))
    )
    (comp (ref "R22")
      (value "贴片电阻")
      (footprint "R0603")
      (description "Resistor")
      (fields (field (name "ALTIUM_VALUE") "10K 1%") (field (name "PUBLISHER") "Altium Limited"))
      (libsource (lib "Miscellaneous Devices") (part "Res1"))
    )
    (comp (ref "R23")
      (value "贴片电阻")
      (footprint "R0603")
      (description "Resistor")
      (fields (field (name "ALTIUM_VALUE") "10K 1%") (field (name "PUBLISHER") "Altium Limited"))
      (libsource (lib "Miscellaneous Devices") (part "Res1"))
    )
    (comp (ref "R24")
      (value "贴片电阻")
      (footprint "R0603")
      (description "Resistor")
      (fields (field (name "ALTIUM_VALUE") "10K 1%") (field (name "PUBLISHER") "Altium Limited"))
      (libsource (lib "Miscellaneous Devices") (part "Res1"))
    )
    (comp (ref "R25")
      (value "贴片电阻")
      (footprint "R0603")
      (description "Resistor")
      (fields (field (name "ALTIUM_VALUE") "100K 5%") (field (name "PUBLISHER") "Altium Limited"))
      (libsource (lib "Miscellaneous Devices") (part "Res1"))
    )
    (comp (ref "R26")
      (value "贴片电阻")
      (footprint "R0603")
      (description "Resistor")
      (fields (field (name "ALTIUM_VALUE") "6.8K 1%") (field (name "PUBLISHER") "Altium Limited"))
      (libsource (lib "Miscellaneous Devices") (part "Res1"))
    )
    (comp (ref "R27")
      (value "贴片电阻")
      (footprint "R0603")
      (description "Resistor")
      (fields (field (name "ALTIUM_VALUE") "44.2K 1%") (field (name "PUBLISHER") "Altium Limited"))
      (libsource (lib "Miscellaneous Devices") (part "Res1"))
    )
    (comp (ref "R28")
      (value "贴片电阻")
      (footprint "R0603")
      (description "Resistor")
      (fields (field (name "ALTIUM_VALUE") "26.1K 1%") (field (name "PUBLISHER") "Altium Limited"))
      (libsource (lib "Miscellaneous Devices") (part "Res1"))
    )
    (comp (ref "R29")
      (value "贴片电阻")
      (footprint "R0603")
      (description "Resistor")
      (fields (field (name "ALTIUM_VALUE") "10K 1%") (field (name "PUBLISHER") "Altium Limited"))
      (libsource (lib "Miscellaneous Devices") (part "Res1"))
    )
    (comp (ref "R30")
      (value "贴片电阻")
      (footprint "R0603")
      (description "Resistor")
      (fields (field (name "ALTIUM_VALUE") "10K 1%") (field (name "PUBLISHER") "Altium Limited"))
      (libsource (lib "Miscellaneous Devices") (part "Res1"))
    )
    (comp (ref "R31")
      (value "贴片电阻")
      (footprint "R0603")
      (description "Resistor")
      (fields (field (name "ALTIUM_VALUE") "10K 1%") (field (name "PUBLISHER") "Altium Limited"))
      (libsource (lib "Miscellaneous Devices") (part "Res1"))
    )
    (comp (ref "R32")
      (value "贴片电阻")
      (footprint "R0603")
      (description "Resistor")
      (fields (field (name "ALTIUM_VALUE") "10K 1%") (field (name "PUBLISHER") "Altium Limited"))
      (libsource (lib "Miscellaneous Devices") (part "Res1"))
    )
    (comp (ref "R33")
      (value "贴片电阻")
      (footprint "R0603")
      (description "Resistor")
      (fields (field (name "ALTIUM_VALUE") "10K 1%") (field (name "PUBLISHER") "Altium Limited"))
      (libsource (lib "Miscellaneous Devices") (part "Res1"))
    )
    (comp (ref "R34")
      (value "贴片电阻")
      (footprint "R0603")
      (description "Resistor")
      (fields (field (name "ALTIUM_VALUE") "10K 1%") (field (name "PUBLISHER") "Altium Limited"))
      (libsource (lib "Miscellaneous Devices") (part "Res1"))
    )
    (comp (ref "R35")
      (value "贴片电阻")
      (footprint "R0603")
      (description "Resistor")
      (fields (field (name "ALTIUM_VALUE") "10K 1%") (field (name "PUBLISHER") "Altium Limited"))
      (libsource (lib "Miscellaneous Devices") (part "Res1"))
    )
    (comp (ref "R36")
      (value "贴片电阻")
      (footprint "R0603")
      (description "Resistor")
      (fields (field (name "ALTIUM_VALUE") "10K 1%") (field (name "PUBLISHER") "Altium Limited"))
      (libsource (lib "Miscellaneous Devices") (part "Res1"))
    )
    (comp (ref "R37")
      (value "贴片电阻")
      (footprint "R0603")
      (description "Resistor")
      (fields (field (name "ALTIUM_VALUE") "10K 1%") (field (name "PUBLISHER") "Altium Limited"))
      (libsource (lib "Miscellaneous Devices") (part "Res1"))
    )
    (comp (ref "R38")
      (value "贴片电阻")
      (footprint "R0603")
      (description "Resistor")
      (fields (field (name "ALTIUM_VALUE") "10K 1%") (field (name "PUBLISHER") "Altium Limited"))
      (libsource (lib "Miscellaneous Devices") (part "Res1"))
    )
    (comp (ref "R39")
      (value "贴片电阻")
      (footprint "R0603")
      (description "Resistor")
      (fields (field (name "ALTIUM_VALUE") "10K 1%") (field (name "PUBLISHER") "Altium Limited"))
      (libsource (lib "Miscellaneous Devices") (part "Res1"))
    )
    (comp (ref "R40")
      (value "贴片电阻")
      (footprint "R0603")
      (description "Resistor")
      (fields (field (name "ALTIUM_VALUE") "1M 5%") (field (name "PUBLISHER") "Altium Limited"))
      (libsource (lib "Miscellaneous Devices") (part "Res1"))
    )
    (comp (ref "R41")
      (value "贴片电阻")
      (footprint "R0603")
      (description "Resistor")
      (fields (field (name "ALTIUM_VALUE") "1M 5%") (field (name "PUBLISHER") "Altium Limited"))
      (libsource (lib "Miscellaneous Devices") (part "Res1"))
    )
    (comp (ref "S1")
      (value "贴片轻触按钮")
      (footprint "Touch button")
      (description "Switch")
      (fields (field (name "ALTIUM_VALUE") "3.5*6*2.5mm") (field (name "PUBLISHER") "Altium Limited"))
      (libsource (lib "Miscellaneous Devices") (part "SW-PB"))
    )
    (comp (ref "S2")
      (value "贴片轻触按钮")
      (footprint "Touch button")
      (description "Switch")
      (fields (field (name "ALTIUM_VALUE") "3.5*6*2.5mm") (field (name "PUBLISHER") "Altium Limited"))
      (libsource (lib "Miscellaneous Devices") (part "SW-PB"))
    )
    (comp (ref "U1")
      (value "LS1C300B_176A")
      (footprint "QFP176")
      (description "龙芯1C300B QFP176A")
      (fields (field (name "ALTIUM_VALUE") "LS1C300B_176A"))
      (libsource (lib "LGHLIB") (part "LS1C300B_176A"))
    )
    (comp (ref "U2")
      (value "复位延时芯片")
      (footprint "SOT-143")
      (fields (field (name "ALTIUM_VALUE") "MAX811"))
      (libsource (lib "LGHLIB") (part "MAX811"))
    )
    (comp (ref "U3")
      (value "SDRAM")
      (footprint "TSOP54")
      (description "ISSI 公司SDRAM ， 166, 133, 100 MHz")
      (fields (field (name "ALTIUM_VALUE") "V54C3256164VHI6/IS42S16400-7T"))
      (libsource (lib "LGHLIB") (part "IS42S16400"))
    )
    (comp (ref "U4")
      (value "NOR FLASH")
      (footprint "SOIC-8-N")
      (description "nor flash W25Q64....华邦")
      (fields (field (name "ALTIUM_VALUE") "W25Q80"))
      (libsource (lib "LGHLIB") (part "W25Q80"))
    )
    (comp (ref "U5")
      (value "电源稳压芯片")
      (footprint "SOIC-8")
      (description "电源稳压芯片MPS,2A，18V的同步整流降压转换器")
      (fields (field (name "ALTIUM_VALUE") "MP1482DS"))
      (libsource (lib "LGHLIB") (part "MP1482"))
    )
    (comp (ref "U6")
      (value "通信芯片")
      (footprint "SOP28")
      (description "USB to Print Port / Parallel")
      (fields (field (name "ALTIUM_VALUE") "CH341A"))
      (libsource (lib "*") (part "CH341S_P"))
    )
    (comp (ref "U7")
      (value "USB座子")
      (footprint "USB-type A")
      (fields (field (name "ALTIUM_VALUE") "USB-type A座子"))
      (libsource (lib "*") (part "USB"))
    )
    (comp (ref "U8")
      (value "电源稳压芯片")
      (footprint "SOIC-8")
      (description "电源稳压芯片MPS,2A，18V的同步整流降压转换器")
      (fields (field (name "ALTIUM_VALUE") "MP1482DS"))
      (libsource (lib "LGHLIB") (part "MP1482"))
    )
    (comp (ref "Y1")
      (value "直插晶振")
      (footprint "HC-49S")
      (description "Crystal Oscillator")
      (fields (field (name "ALTIUM_VALUE") "24MHz") (field (name "PUBLISHER") "Altium Limited"))
      (libsource (lib "Miscellaneous Devices") (part "XTAL"))
    )
    (comp (ref "Y2")
      (value "直插晶振")
      (footprint "TC-38")
      (description "Crystal Oscillator")
      (fields (field (name "ALTIUM_VALUE") "32.768KHz") (field (name "PUBLISHER") "Altium Limited"))
      (libsource (lib "Miscellaneous Devices") (part "XTAL"))
    )
    (comp (ref "Y3")
      (value "直插晶振")
      (footprint "HC-49S")
      (description "Crystal")
      (fields (field (name "ALTIUM_VALUE") "12MHz"))
      (libsource (lib "*") (part "CRYSTAL"))
    )
  )
  (nets
    (net (code "1") (name "/3") (class "Default")
      (node (ref "P1") (pin "3") (pinfunction "3_3") (pintype "passive"))
      (node (ref "U1") (pin "3") (pinfunction "LCD_CLK_/PIX_CLK/GPIO76_3") (pintype "passive"))
    )
    (net (code "2") (name "/4") (class "Default")
      (node (ref "P1") (pin "4") (pinfunction "4_4") (pintype "passive"))
      (node (ref "U1") (pin "4") (pinfunction "LCD_HSYNC_/GPIO74_/SPI0_CS1/__Sdio_Dat2__/UART0_RX_/PWM2_/I2C_SDA1_/SDRAM_CS1_4") (pintype "passive"))
    )
    (net (code "3") (name "/5") (class "Default")
      (node (ref "P1") (pin "5") (pinfunction "5_5") (pintype "passive"))
      (node (ref "U1") (pin "5") (pinfunction "LCD_VSYNC_/GPIO75_/SPI0_CS2/__Sdio_Dat3_/_UART0_TX_/PWM3_/I2C_SCL1_5") (pintype "passive"))
    )
    (net (code "4") (name "/6") (class "Default")
      (node (ref "P1") (pin "6") (pinfunction "6_6") (pintype "passive"))
      (node (ref "U1") (pin "6") (pinfunction "LCD_EN_/GPIO77_6") (pintype "passive"))
    )
    (net (code "5") (name "/7") (class "Default")
      (node (ref "P1") (pin "7") (pinfunction "7_7") (pintype "passive"))
      (node (ref "U1") (pin "7") (pinfunction "LCD_D0/LCD_B3/GPIO58_/UART4_RX/_UART0_CTS_7") (pintype "passive"))
    )
    (net (code "6") (name "/8") (class "Default")
      (node (ref "P1") (pin "8") (pinfunction "8_8") (pintype "passive"))
      (node (ref "U1") (pin "8") (pinfunction "LCD_D1/LCD_B4/GPIO59_/UART4_TX/_UART0_RTS_8") (pintype "passive"))
    )
    (net (code "7") (name "/9") (class "Default")
      (node (ref "P1") (pin "9") (pinfunction "9_9") (pintype "passive"))
      (node (ref "U1") (pin "9") (pinfunction "LCD_D2/LCD_B5/GPIO60_/UART5_RX/_UART0_DSR_9") (pintype "passive"))
    )
    (net (code "8") (name "/10") (class "Default")
      (node (ref "P1") (pin "10") (pinfunction "10_10") (pintype "passive"))
      (node (ref "U1") (pin "10") (pinfunction "LCD_D3/_LCD_B6_/GPIO61_/UART5_TX/_UART0_DTR_10") (pintype "passive"))
    )
    (net (code "9") (name "/12") (class "Default")
      (node (ref "P1") (pin "12") (pinfunction "12_12") (pintype "passive"))
      (node (ref "U1") (pin "12") (pinfunction "LCD_D4_/LCD_B7_/GPIO62_/UART6_RX/__UART0_DCD_12") (pintype "passive"))
    )
    (net (code "10") (name "/13") (class "Default")
      (node (ref "P1") (pin "13") (pinfunction "13_13") (pintype "passive"))
      (node (ref "U1") (pin "13") (pinfunction "LCD_D5_/LCD_G2_/GPIO63_/UART6_TX/UART0_RI_13") (pintype "passive"))
    )
    (net (code "11") (name "/14") (class "Default")
      (node (ref "P1") (pin "14") (pinfunction "14_14") (pintype "passive"))
      (node (ref "U1") (pin "14") (pinfunction "LCD_D6_/LCD_G3_/GPIO64_/UART7_RX_14") (pintype "passive"))
    )
    (net (code "12") (name "/15") (class "Default")
      (node (ref "P1") (pin "15") (pinfunction "15_15") (pintype "passive"))
      (node (ref "U1") (pin "15") (pinfunction "LCD_D7_/LCD_G4_/GPIO65_/UART7_TX_15") (pintype "passive"))
    )
    (net (code "13") (name "/16") (class "Default")
      (node (ref "P1") (pin "16") (pinfunction "16_16") (pintype "passive"))
      (node (ref "U1") (pin "16") (pinfunction "LCD_D8_/LCD_G5_/GPIO66_/UART8_RX_16") (pintype "passive"))
    )
    (net (code "14") (name "/17") (class "Default")
      (node (ref "P1") (pin "17") (pinfunction "17_17") (pintype "passive"))
      (node (ref "U1") (pin "17") (pinfunction "LCD_D9_/LCD_G6_/GPIO67_/UART8_TX_17") (pintype "passive"))
    )
    (net (code "15") (name "/19") (class "Default")
      (node (ref "P1") (pin "19") (pinfunction "19_19") (pintype "passive"))
      (node (ref "U1") (pin "19") (pinfunction "LCD_D10__/LCD_G7/_GPIO68_/UART9_RX/__UART8_CTS_19") (pintype "passive"))
    )
    (net (code "16") (name "/20") (class "Default")
      (node (ref "P1") (pin "20") (pinfunction "20_20") (pintype "passive"))
      (node (ref "U1") (pin "20") (pinfunction "LCD_R3__/LCD_D11_/GPIO69_/UART9_TX/__UART8_RTS_20") (pintype "passive"))
    )
    (net (code "17") (name "/21") (class "Default")
      (node (ref "P1") (pin "21") (pinfunction "21_21") (pintype "passive"))
      (node (ref "U1") (pin "21") (pinfunction "LCD_D12__/LCD_R4__/GPIO70_/UART10_RX/__UART8_DSR_21") (pintype "passive"))
    )
    (net (code "18") (name "/23") (class "Default")
      (node (ref "P1") (pin "22") (pinfunction "22_22") (pintype "passive"))
      (node (ref "U1") (pin "23") (pinfunction "LCD_D13_/LCD_R5__/GPIO71_/UART10_TX/__UART8_DTR_23") (pintype "passive"))
    )
    (net (code "19") (name "/24") (class "Default")
      (node (ref "P1") (pin "23") (pinfunction "23_23") (pintype "passive"))
      (node (ref "U1") (pin "24") (pinfunction "LCD_D14__/LCD_R6__/GPIO72_/UART11_RX/__UART8_DCD_24") (pintype "passive"))
    )
    (net (code "20") (name "/25") (class "Default")
      (node (ref "P1") (pin "24") (pinfunction "24_24") (pintype "passive"))
      (node (ref "U1") (pin "25") (pinfunction "LCD_D15__/LCD_R7__/GPIO73_/UART11_TX/__UART8_RI_25") (pintype "passive"))
    )
    (net (code "21") (name "/70") (class "Default")
      (node (ref "P4") (pin "2") (pinfunction "2_2") (pintype "passive"))
      (node (ref "U1") (pin "70") (pinfunction "I2S_DI_/GPIO87_/UART7_RX_70") (pintype "passive"))
    )
    (net (code "22") (name "/71") (class "Default")
      (node (ref "P4") (pin "3") (pinfunction "3_3") (pintype "passive"))
      (node (ref "U1") (pin "71") (pinfunction "I2S_DO_/GPIO88_/UART7_TX_71") (pintype "passive"))
    )
    (net (code "23") (name "/72") (class "Default")
      (node (ref "P4") (pin "4") (pinfunction "4_4") (pintype "passive"))
      (node (ref "U1") (pin "72") (pinfunction "I2S_LRCK_/GPIO89_/UART8_RX_72") (pintype "passive"))
    )
    (net (code "24") (name "/73") (class "Default")
      (node (ref "P4") (pin "5") (pinfunction "5_5") (pintype "passive"))
      (node (ref "U1") (pin "73") (pinfunction "I2S_BCLK_/GPIO90_/UART8_TX_73") (pintype "passive"))
    )
    (net (code "25") (name "/74") (class "Default")
      (node (ref "P4") (pin "6") (pinfunction "6_6") (pintype "passive"))
      (node (ref "U1") (pin "74") (pinfunction "I2C_SDA0_/GPIO85_/UART9_RX/__UART8_CTS_74") (pintype "passive"))
    )
    (net (code "26") (name "/75") (class "Default")
      (node (ref "P4") (pin "7") (pinfunction "7_7") (pintype "passive"))
      (node (ref "U1") (pin "75") (pinfunction "I2C_SCL0__/GPIO86_/UART9_TX/__UART8_RTS_75") (pintype "passive"))
    )
    (net (code "27") (name "/76") (class "Default")
      (node (ref "P4") (pin "8") (pinfunction "8_8") (pintype "passive"))
      (node (ref "U1") (pin "76") (pinfunction "I2S_MCLK_/GPIO91_76") (pintype "passive"))
    )
    (net (code "28") (name "/77") (class "Default")
      (node (ref "P4") (pin "9") (pinfunction "9_9") (pintype "passive"))
      (node (ref "U1") (pin "77") (pinfunction "PWM1_/GPIO92_/ADC_YN_77") (pintype "passive"))
    )
    (net (code "29") (name "/78") (class "Default")
      (node (ref "P4") (pin "10") (pinfunction "10_10") (pintype "passive"))
      (node (ref "U1") (pin "78") (pinfunction "PWM0/__CAMCLKOUT__/GPIO06_/ADC_XN_78") (pintype "passive"))
    )
    (net (code "30") (name "/79") (class "Default")
      (node (ref "P4") (pin "11") (pinfunction "11_11") (pintype "passive"))
      (node (ref "U1") (pin "79") (pinfunction "SPI0_CS2_/GPIO83_/Sdio_Dat3_79") (pintype "passive"))
    )
    (net (code "31") (name "/82") (class "Default")
      (node (ref "P4") (pin "14") (pinfunction "14_14") (pintype "passive"))
      (node (ref "U1") (pin "82") (pinfunction "ADC_VREF_82") (pintype "passive"))
    )
    (net (code "32") (name "/85") (class "Default")
      (node (ref "P4") (pin "15") (pinfunction "15_15") (pintype "passive"))
      (node (ref "U1") (pin "85") (pinfunction "ADC_D0_85") (pintype "passive"))
    )
    (net (code "33") (name "/86") (class "Default")
      (node (ref "P4") (pin "16") (pinfunction "16_16") (pintype "passive"))
      (node (ref "U1") (pin "86") (pinfunction "ADC_D1_86") (pintype "passive"))
    )
    (net (code "34") (name "/87") (class "Default")
      (node (ref "P4") (pin "17") (pinfunction "17_17") (pintype "passive"))
      (node (ref "U1") (pin "87") (pinfunction "ADC_XP_87") (pintype "passive"))
    )
    (net (code "35") (name "/88") (class "Default")
      (node (ref "P4") (pin "18") (pinfunction "18_18") (pintype "passive"))
      (node (ref "U1") (pin "88") (pinfunction "ADC_YP_88") (pintype "passive"))
    )
    (net (code "36") (name "/89") (class "Default")
      (node (ref "P4") (pin "19") (pinfunction "19_19") (pintype "passive"))
      (node (ref "U1") (pin "89") (pinfunction "SPI0_CS3_/GPIO84_/CAMCLKOUT_/UART10_RX/__UART8_DSR_89") (pintype "passive"))
    )
    (net (code "37") (name "/93") (class "Default")
      (node (ref "P4") (pin "20") (pinfunction "20_20") (pintype "passive"))
      (node (ref "U1") (pin "93") (pinfunction "SPI0_CS1_/GPIO82_/Sdio_Dat2_/UART10_TX/__UART8_DTR_93") (pintype "passive"))
    )
    (net (code "38") (name "/103") (class "Default")
      (node (ref "P4") (pin "23") (pinfunction "23_23") (pintype "passive"))
      (node (ref "U1") (pin "103") (pinfunction "CAMDATA7_/GPIO57_/LCD_R2_/CAN1_TX_/I2C_SCL2_/UART7_RX_103") (pintype "passive"))
    )
    (net (code "39") (name "/104") (class "Default")
      (node (ref "P4") (pin "24") (pinfunction "24_24") (pintype "passive"))
      (node (ref "U1") (pin "104") (pinfunction "CAMDATA6_/GPIO56_/LCD_R1_/CAN1_RX_/I2C_SDA2_/UART7_TX_104") (pintype "passive"))
    )
    (net (code "40") (name "/105") (class "Default")
      (node (ref "P4") (pin "25") (pinfunction "25_25") (pintype "passive"))
      (node (ref "U1") (pin "105") (pinfunction "CAMDATA5_/GPIO55_/LCD_R0_/CAN0_TX_/I2C_SCL1_/UART8_RX_105") (pintype "passive"))
    )
    (net (code "41") (name "/106") (class "Default")
      (node (ref "P4") (pin "26") (pinfunction "26_26") (pintype "passive"))
      (node (ref "U1") (pin "106") (pinfunction "CAMDATA4_/GPIO54_/LCD_G1_/CAN0_RX_/I2C_SDA1_/UART8_TX_106") (pintype "passive"))
    )
    (net (code "42") (name "/107") (class "Default")
      (node (ref "P4") (pin "27") (pinfunction "27_27") (pintype "passive"))
      (node (ref "U1") (pin "107") (pinfunction "CAMDATA3_/GPIO53_/LCD_G0_/CAMCLKOUT_/PWM3_/UART9_RX/__UART8_CTS_107") (pintype "passive"))
    )
    (net (code "43") (name "/108") (class "Default")
      (node (ref "P4") (pin "28") (pinfunction "28_28") (pintype "passive"))
      (node (ref "U1") (pin "108") (pinfunction "CAMDATA2_/GPIO52_/LCD_B2_/SPI1_CS3_/PWM2_/UART9_TX/__UART8_RTS_108") (pintype "passive"))
    )
    (net (code "44") (name "/109") (class "Default")
      (node (ref "P6") (pin "13") (pinfunction "13_13") (pintype "passive"))
      (node (ref "U1") (pin "109") (pinfunction "CAMDATA1_/GPIO51_/LCD_B1_/SPI1_CS2_/I2C_SCL2_/UART10_RX/__UART8_DSR_109") (pintype "passive"))
    )
    (net (code "45") (name "/110") (class "Default")
      (node (ref "P6") (pin "14") (pinfunction "14_14") (pintype "passive"))
      (node (ref "U1") (pin "110") (pinfunction "CAMDATA0_/GPIO50_/LCD_B0_/SPI1_CS1_/I2C_SDA2_/UART10_TX/__UART8_DTR_110") (pintype "passive"))
    )
    (net (code "46") (name "/112") (class "Default")
      (node (ref "P6") (pin "12") (pinfunction "12_12") (pintype "passive"))
      (node (ref "U1") (pin "112") (pinfunction "CAMHSYNC_/GPIO49_/NAND_RDY3_/SPI1_CS0_/I2C_SCL1_/UART11_RX/__UART8_DCD_112") (pintype "passive"))
    )
    (net (code "47") (name "/113") (class "Default")
      (node (ref "P6") (pin "9") (pinfunction "9_9") (pintype "passive"))
      (node (ref "U1") (pin "113") (pinfunction "CAMVSYNC_/GPIO48_/NAND_CE#3_/SPI1_MOSI_/I2C_SDA1_/UART11_TX/__UART8_RI_113") (pintype "passive"))
    )
    (net (code "48") (name "/114") (class "Default")
      (node (ref "P6") (pin "10") (pinfunction "10_10") (pintype "passive"))
      (node (ref "U1") (pin "114") (pinfunction "CAMCLKOUT_/GPIO47_/SRAM_A25_/NAND_RDY2_/SPI1_MISO_/PWM3_/UART6_RX/__UART0_DCD_114") (pintype "passive"))
    )
    (net (code "49") (name "/115") (class "Default")
      (node (ref "P6") (pin "7") (pinfunction "7_7") (pintype "passive"))
      (node (ref "U1") (pin "115") (pinfunction "CAMPCLKIN_/GPIO46_/SRAM_A24_/NAND_CE#2_/SPI1_CLK_/PWM2_/UART6_TX/__UART0_RI_115") (pintype "passive"))
    )
    (net (code "50") (name "/116") (class "Default")
      (node (ref "P6") (pin "8") (pinfunction "8_8") (pintype "passive"))
      (node (ref "U1") (pin "116") (pinfunction "NAND_7_/GPIO20_/SPI1_CS1/__Sdio_Dat2__/MAC_MDIO_/CAMDATA0_/I2C_SCL2_116") (pintype "passive"))
    )
    (net (code "51") (name "/117") (class "Default")
      (node (ref "P6") (pin "5") (pinfunction "5_5") (pintype "passive"))
      (node (ref "U1") (pin "117") (pinfunction "NAND_6_/GPIO19_/SPI1_CS2/__Sdio_Dat3__/MAC_MDC_/CAMDATA1_/I2C_SDA2_117") (pintype "passive"))
    )
    (net (code "52") (name "/118(5)") (class "Default")
      (node (ref "P6") (pin "6") (pinfunction "6_6") (pintype "passive"))
      (node (ref "R16") (pin "2") (pinfunction "2_2") (pintype "passive"))
      (node (ref "U1") (pin "118") (pinfunction "NAND_5_/GPIO18_/UART1_TX_/UART3_TX_/CAMDATA2_/PWM2_118") (pintype "passive"))
    )
    (net (code "53") (name "/119(4)") (class "Default")
      (node (ref "P6") (pin "3") (pinfunction "3_3") (pintype "passive"))
      (node (ref "R15") (pin "2") (pinfunction "2_2") (pintype "passive"))
      (node (ref "U1") (pin "119") (pinfunction "NAND_4_/GPIO17_/UART1_RX_/UART3_RX_/CAMDATA3_/PWM3_119") (pintype "passive"))
    )
    (net (code "54") (name "/120") (class "Default")
      (node (ref "P6") (pin "4") (pinfunction "4_4") (pintype "passive"))
      (node (ref "U1") (pin "120") (pinfunction "NAND_3_/GPIO16_/SPI1_CS0/__Sdio_Dat1__/CAN1_TX_/CAMDATA4_/I2S_LRCK_120") (pintype "passive"))
    )
    (net (code "55") (name "/121") (class "Default")
      (node (ref "P6") (pin "1") (pinfunction "1_1") (pintype "passive"))
      (node (ref "U1") (pin "121") (pinfunction "NAND_2_/GPIO15_/SPI1_MOSI/__Sdio_Dat0/CAN1_RX_/CAMDATA5_/I2S_DO_121") (pintype "passive"))
    )
    (net (code "56") (name "/122") (class "Default")
      (node (ref "P6") (pin "2") (pinfunction "2_2") (pintype "passive"))
      (node (ref "U1") (pin "122") (pinfunction "NAND_1_/GPIO14_/SPI1_MISO/__Sdio_Cmd__/CAN0_TX_/CAMDATA6_/I2S_BCLK_122") (pintype "passive"))
    )
    (net (code "57") (name "/123") (class "Default")
      (node (ref "P3") (pin "13") (pinfunction "13_13") (pintype "passive"))
      (node (ref "U1") (pin "123") (pinfunction "NAND_0_/GPIO13_/SPI1_CLK/__Sdio_clk__/CAN0_RX_/CAMDATA7_/I2S_MCLK_/GPIO_123") (pintype "passive"))
    )
    (net (code "58") (name "/127") (class "Default")
      (node (ref "P3") (pin "9") (pinfunction "9_9") (pintype "passive"))
      (node (ref "U1") (pin "127") (pinfunction "NAND_RDY_/GPIO07_127") (pintype "passive"))
    )
    (net (code "59") (name "/128") (class "Default")
      (node (ref "P3") (pin "10") (pinfunction "10_10") (pintype "passive"))
      (node (ref "U1") (pin "128") (pinfunction "NAND_CLE_/GPIO08_/GPIO_128") (pintype "passive"))
    )
    (net (code "60") (name "/129") (class "Default")
      (node (ref "P3") (pin "7") (pinfunction "7_7") (pintype "passive"))
      (node (ref "U1") (pin "129") (pinfunction "NAND_ALE_/GPIO09_/GPIO_129") (pintype "passive"))
    )
    (net (code "61") (name "/130") (class "Default")
      (node (ref "P3") (pin "8") (pinfunction "8_8") (pintype "passive"))
      (node (ref "U1") (pin "130") (pinfunction "NAND_RD#_/GPIO10_/GPIO_130") (pintype "passive"))
    )
    (net (code "62") (name "/132") (class "Default")
      (node (ref "P3") (pin "6") (pinfunction "6_6") (pintype "passive"))
      (node (ref "U1") (pin "132") (pinfunction "NAND_CE#_/GPIO11_/GPIO_132") (pintype "passive"))
    )
    (net (code "63") (name "/133") (class "Default")
      (node (ref "P3") (pin "3") (pinfunction "3_3") (pintype "passive"))
      (node (ref "U1") (pin "133") (pinfunction "NAND_WR#_/GPIO12_/GPIO_133") (pintype "passive"))
    )
    (net (code "64") (name "/134") (class "Default")
      (node (ref "P3") (pin "4") (pinfunction "4_4") (pintype "passive"))
      (node (ref "U1") (pin "134") (pinfunction "MAC_TXEN_/GPIO21_/I2S_MCLK_/NAND_CLE_/I2C_SDA2_/CAN0_RX_/UART8_RX_134") (pintype "passive"))
    )
    (net (code "65") (name "/135") (class "Default")
      (node (ref "P3") (pin "1") (pinfunction "1_1") (pintype "passive"))
      (node (ref "U1") (pin "135") (pinfunction "MAC_TXD0_/GPIO23_/I2S_DO_/NAND_ALE_/UART0_RX_/CAN1_RX_/UART4_RX/__UART0_CTS_135") (pintype "passive"))
    )
    (net (code "66") (name "/136") (class "Default")
      (node (ref "P3") (pin "2") (pinfunction "2_2") (pintype "passive"))
      (node (ref "U1") (pin "136") (pinfunction "MAC_TXD1_/GPIO24_/I2S_LRCK_/NAND_WR#_/UART0_TX_/CAN1_TX_/UART4_TX/__UART0_RTS_136") (pintype "passive"))
    )
    (net (code "67") (name "/137") (class "Default")
      (node (ref "P2") (pin "27") (pinfunction "27_27") (pintype "passive"))
      (node (ref "U1") (pin "137") (pinfunction "MAC_RXER_/GPIO25_/I2S_DI_/NAND_RDY0_/I2C_SDA1_/CAMCLKOUT_/UART5_RX/__UART0_DSR_137") (pintype "passive"))
    )
    (net (code "68") (name "/138") (class "Default")
      (node (ref "P2") (pin "28") (pinfunction "28_28") (pintype "passive"))
      (node (ref "U1") (pin "138") (pinfunction "MAC_RXDV_/GPIO26_/SPI1_CS3_/NAND_CE#0_/I2C_SCL1_/CAMPCLKIN_/UART5_TX/__UART0_DTR__/GPIO_138") (pintype "passive"))
    )
    (net (code "69") (name "/139") (class "Default")
      (node (ref "P2") (pin "25") (pinfunction "25_25") (pintype "passive"))
      (node (ref "U1") (pin "139") (pinfunction "MAC_RXD0_/GPIO27_/I2C_SDA_/PWM2_/UART2_RX_/CAMVSYNC_/UART6_RX/__UART0_DCD__/GPIO_139") (pintype "passive"))
    )
    (net (code "70") (name "/140") (class "Default")
      (node (ref "P2") (pin "26") (pinfunction "26_26") (pintype "passive"))
      (node (ref "U1") (pin "140") (pinfunction "MAC_RXD1_/GPIO28_/I2C_SCL_/PWM3_/UART2_TX_/CAMHSYNC_/UART6_TX/__UART0_RI__/GPIO_140") (pintype "passive"))
    )
    (net (code "71") (name "/141") (class "Default")
      (node (ref "P2") (pin "23") (pinfunction "23_23") (pintype "passive"))
      (node (ref "U1") (pin "141") (pinfunction "MAC_MDC_/GPIO29_/CAMDATA7_/NAND_CE#1_/PWM2_/I2C_SCL1_/UART8_TX_/GPIO_141") (pintype "passive"))
    )
    (net (code "72") (name "/143") (class "Default")
      (node (ref "P2") (pin "21") (pinfunction "21_21") (pintype "passive"))
      (node (ref "U1") (pin "143") (pinfunction "MAC_MDIO_/GPIO30_/CAMDATA6_/NAND_RDY1_/LCD_B0_/I2C_SDA1_/GPIO_143") (pintype "passive"))
    )
    (net (code "73") (name "/144") (class "Default")
      (node (ref "P2") (pin "22") (pinfunction "22_22") (pintype "passive"))
      (node (ref "U1") (pin "144") (pinfunction "MAC_RXD2_/GPIO31_/CAMDATA5_/NAND_CS#2_/LCD_B1_/CAN1_RX_/UART11_RX/__UART8_DCD__/GPIO_144") (pintype "passive"))
    )
    (net (code "74") (name "/145") (class "Default")
      (node (ref "D3") (pin "2") (pinfunction "K_2") (pintype "passive"))
      (node (ref "P2") (pin "19") (pinfunction "19_19") (pintype "passive"))
      (node (ref "U1") (pin "145") (pinfunction "MAC_TXD2_/GPIO32_/CAMDATA4_/NAND_RDY2_/LCD_B2_/CAN1_TX_/UART11_TX/__UART8_RI_145") (pintype "passive"))
    )
    (net (code "75") (name "/146") (class "Default")
      (node (ref "P2") (pin "20") (pinfunction "20_20") (pintype "passive"))
      (node (ref "U1") (pin "146") (pinfunction "MAC_RXD3_/GPIO33_/CAMDATA3_/UART3_RX_/LCD_G0_/SPI1_CLK/__Sdio_clk_146") (pintype "passive"))
    )
    (net (code "76") (name "/147") (class "Default")
      (node (ref "P2") (pin "17") (pinfunction "17_17") (pintype "passive"))
      (node (ref "U1") (pin "147") (pinfunction "MAC_TXD3_/GPIO34_/CAMDATA2_/UART3_TX_/LCD_G1_/SPI1_MISO/__Sdio_Cmd_147") (pintype "passive"))
    )
    (net (code "77") (name "/148") (class "Default")
      (node (ref "P2") (pin "18") (pinfunction "18_18") (pintype "passive"))
      (node (ref "U1") (pin "148") (pinfunction "MAC_TXC_/GPIO22_/I2S_BCLK_/NAND_RD#_/I2C_SCL2_/CANO_TX_/SDRAM_CS1_148") (pintype "passive"))
    )
    (net (code "78") (name "/151") (class "Default")
      (node (ref "P2") (pin "13") (pinfunction "13_13") (pintype "passive"))
      (node (ref "U1") (pin "151") (pinfunction "MAC_CRS__(ONLY_MII)_/GPIO35_/CAMDATA1_/PWM1_/LCD_R0_/SPI1_MOSI/__Sdio_Dat0_151") (pintype "passive"))
    )
    (net (code "79") (name "/157") (class "Default")
      (node (ref "P2") (pin "11") (pinfunction "11_11") (pintype "passive"))
      (node (ref "U1") (pin "157") (pinfunction "OTG_DM_157") (pintype "passive"))
    )
    (net (code "80") (name "/158") (class "Default")
      (node (ref "P2") (pin "10") (pinfunction "10_10") (pintype "passive"))
      (node (ref "U1") (pin "158") (pinfunction "OTG_DP_158") (pintype "passive"))
    )
    (net (code "81") (name "/160") (class "Default")
      (node (ref "P2") (pin "8") (pinfunction "8_8") (pintype "passive"))
      (node (ref "U1") (pin "160") (pinfunction "OTG_VBUS_160") (pintype "passive"))
    )
    (net (code "82") (name "/161") (class "Default")
      (node (ref "P2") (pin "7") (pinfunction "7_7") (pintype "passive"))
      (node (ref "U1") (pin "161") (pinfunction "OTG_ID_161") (pintype "passive"))
    )
    (net (code "83") (name "/168") (class "Default")
      (node (ref "P2") (pin "6") (pinfunction "6_6") (pintype "passive"))
      (node (ref "U1") (pin "168") (pinfunction "USB_DM_168") (pintype "passive"))
    )
    (net (code "84") (name "/169") (class "Default")
      (node (ref "P2") (pin "3") (pinfunction "3_3") (pintype "passive"))
      (node (ref "U1") (pin "169") (pinfunction "USB_DP_169") (pintype "passive"))
    )
    (net (code "85") (name "/CH_CLK_SPI0_CLK") (class "Default")
      (node (ref "P7") (pin "4") (pinfunction "4_4") (pintype "passive"))
      (node (ref "U6") (pin "18") (pinfunction "D3_18") (pintype "bidirectional"))
    )
    (net (code "86") (name "/CH_MISO_SPI0_MISO") (class "Default")
      (node (ref "P7") (pin "2") (pinfunction "2_2") (pintype "passive"))
      (node (ref "U6") (pin "22") (pinfunction "D7_22") (pintype "bidirectional"))
    )
    (net (code "87") (name "/CH_MOSI_SPI0_MOSI") (class "Default")
      (node (ref "P7") (pin "3") (pinfunction "3_3") (pintype "passive"))
      (node (ref "U6") (pin "20") (pinfunction "D5_20") (pintype "bidirectional"))
    )
    (net (code "88") (name "/CH_SDA") (class "Default")
      (node (ref "P7") (pin "1") (pinfunction "1_1") (pintype "passive"))
      (node (ref "U6") (pin "23") (pinfunction "SDA_23") (pintype "bidirectional"))
    )
    (net (code "89") (name "/EJTAG_RST") (class "Default")
      (node (ref "P5") (pin "1") (pinfunction "TRST_N_1") (pintype "passive"))
      (node (ref "R34") (pin "1") (pinfunction "1_1") (pintype "passive"))
      (node (ref "R35") (pin "1") (pinfunction "1_1") (pintype "passive"))
      (node (ref "U1") (pin "100") (pinfunction "EJTAG_RST_/GPIO05_/CAMDATA0_/I2C_SCL2_/PWM1_/UART2_TX_/GPIO_100") (pintype "passive"))
    )
    (net (code "90") (name "/EJTAG_SEL") (class "Default")
      (node (ref "R38") (pin "1") (pinfunction "1_1") (pintype "passive"))
      (node (ref "R39") (pin "1") (pinfunction "1_1") (pintype "passive"))
      (node (ref "U1") (pin "95") (pinfunction "EJTAG_SEL_/GPIO00_/CAMCLKOUT_/I2C_SDA0_/CAN0_RX_/UART3_RX_/SDRAM_CS1_/GPIO_95") (pintype "passive"))
    )
    (net (code "91") (name "/EJTAG_TCK") (class "Default")
      (node (ref "P5") (pin "5") (pinfunction "TCK_5") (pintype "passive"))
      (node (ref "R30") (pin "1") (pinfunction "1_1") (pintype "passive"))
      (node (ref "U1") (pin "96") (pinfunction "EJTAG_TCK_/GPIO01_/CAMPCLKIN_/I2C_SCL0_/CAN0_TX_/UART3_TX_/GPIO_96") (pintype "passive"))
    )
    (net (code "92") (name "/EJTAG_TDI") (class "Default")
      (node (ref "P5") (pin "2") (pinfunction "TDI_2") (pintype "passive"))
      (node (ref "R33") (pin "1") (pinfunction "1_1") (pintype "passive"))
      (node (ref "U1") (pin "99") (pinfunction "EJTAG_TDI_/GPIO02_/CAMVSYNC_/I2C_SDA1_/CAN1_RX_/UART1_RX_/GPIO_99") (pintype "passive"))
    )
    (net (code "93") (name "/EJTAG_TDO") (class "Default")
      (node (ref "P5") (pin "3") (pinfunction "TDO_3") (pintype "passive"))
      (node (ref "R32") (pin "1") (pinfunction "1_1") (pintype "passive"))
      (node (ref "U1") (pin "98") (pinfunction "EJTAG_TDO_/GPIO03_/CAMHSYNC_/I2C_SCL1_/CAN1_TX_/UART1_TX_/GPIO_98") (pintype "passive"))
    )
    (net (code "94") (name "/EJTAG_TMS") (class "Default")
      (node (ref "P5") (pin "4") (pinfunction "TMS_4") (pintype "passive"))
      (node (ref "R31") (pin "1") (pinfunction "1_1") (pintype "passive"))
      (node (ref "U1") (pin "97") (pinfunction "EJTAG_TMS_/GPIO04_/CAMDATA1_/I2C_SDA2_/PWM0_/UART2_RX_/GPIO_97") (pintype "passive"))
    )
    (net (code "95") (name "/FLASH_CS0") (class "Default")
      (node (ref "P7") (pin "7") (pinfunction "7_7") (pintype "passive"))
      (node (ref "P7") (pin "8") (pinfunction "8_8") (pintype "passive"))
      (node (ref "R6") (pin "2") (pinfunction "2_2") (pintype "passive"))
      (node (ref "U4") (pin "1") (pinfunction "~{CS}_1") (pintype "passive"))
    )
    (net (code "96") (name "/JTAG_SEL") (class "Default")
      (node (ref "R36") (pin "1") (pinfunction "1_1") (pintype "passive"))
      (node (ref "R37") (pin "1") (pinfunction "1_1") (pintype "passive"))
      (node (ref "U1") (pin "126") (pinfunction "JTAG_SEL_/SDRAM_CS1_/UART6_TX/__UART0_RI_126") (pintype "passive"))
    )
    (net (code "97") (name "/RTCI") (class "Default")
      (node (ref "C3") (pin "2") (pinfunction "2_2") (pintype "passive"))
      (node (ref "R41") (pin "2") (pinfunction "2_2") (pintype "passive"))
      (node (ref "U1") (pin "175") (pinfunction "RTC_CLK_I_175") (pintype "passive"))
      (node (ref "Y2") (pin "2") (pinfunction "OSC2_2") (pintype "passive"))
    )
    (net (code "98") (name "/RTCO") (class "Default")
      (node (ref "C4") (pin "2") (pinfunction "2_2") (pintype "passive"))
      (node (ref "R41") (pin "1") (pinfunction "1_1") (pintype "passive"))
      (node (ref "U1") (pin "174") (pinfunction "RTC_CLK_O_174") (pintype "passive"))
      (node (ref "Y2") (pin "1") (pinfunction "OSC1_1") (pintype "passive"))
    )
    (net (code "99") (name "/RTC_VDDA") (class "Default")
      (node (ref "D1") (pin "2") (pinfunction "K_2") (pintype "passive"))
      (node (ref "P2") (pin "4") (pinfunction "4_4") (pintype "passive"))
      (node (ref "U1") (pin "176") (pinfunction "RTC_VR_VDDA_176") (pintype "passive"))
    )
    (net (code "100") (name "/SDRAM_A0") (class "Default")
      (node (ref "U1") (pin "67") (pinfunction "SD_A00/__SRAM_A00_67") (pintype "passive"))
      (node (ref "U3") (pin "23") (pinfunction "A0_23") (pintype "passive"))
    )
    (net (code "101") (name "/SDRAM_A1") (class "Default")
      (node (ref "U1") (pin "66") (pinfunction "SD_A01/__SRAM_A01_66") (pintype "passive"))
      (node (ref "U3") (pin "24") (pinfunction "A1_24") (pintype "passive"))
    )
    (net (code "102") (name "/SDRAM_A2") (class "Default")
      (node (ref "U1") (pin "65") (pinfunction "SD_A02/__SRAM_A02_65") (pintype "passive"))
      (node (ref "U3") (pin "25") (pinfunction "A2_25") (pintype "passive"))
    )
    (net (code "103") (name "/SDRAM_A3") (class "Default")
      (node (ref "U1") (pin "64") (pinfunction "SD_A03/__SRAM_A03_64") (pintype "passive"))
      (node (ref "U3") (pin "26") (pinfunction "A3_26") (pintype "passive"))
    )
    (net (code "104") (name "/SDRAM_A4") (class "Default")
      (node (ref "U1") (pin "63") (pinfunction "SD_A04/__SRAM_A04_63") (pintype "passive"))
      (node (ref "U3") (pin "29") (pinfunction "A4_29") (pintype "passive"))
    )
    (net (code "105") (name "/SDRAM_A5") (class "Default")
      (node (ref "U1") (pin "62") (pinfunction "SD_A05/__SRAM_A05_62") (pintype "passive"))
      (node (ref "U3") (pin "30") (pinfunction "A5_30") (pintype "passive"))
    )
    (net (code "106") (name "/SDRAM_A6") (class "Default")
      (node (ref "U1") (pin "61") (pinfunction "SD_A06/__SRAM_A06_61") (pintype "passive"))
      (node (ref "U3") (pin "31") (pinfunction "A6_31") (pintype "passive"))
    )
    (net (code "107") (name "/SDRAM_A7") (class "Default")
      (node (ref "U1") (pin "60") (pinfunction "SD_A07/__SRAM_A07_60") (pintype "passive"))
      (node (ref "U3") (pin "32") (pinfunction "A7_32") (pintype "passive"))
    )
    (net (code "108") (name "/SDRAM_A8") (class "Default")
      (node (ref "U1") (pin "59") (pinfunction "SD_A08/__SRAM_A08_59") (pintype "passive"))
      (node (ref "U3") (pin "33") (pinfunction "A8_33") (pintype "passive"))
    )
    (net (code "109") (name "/SDRAM_A9") (class "Default")
      (node (ref "U1") (pin "58") (pinfunction "SD_A09/__SRAM_A09_58") (pintype "passive"))
      (node (ref "U3") (pin "34") (pinfunction "A9_34") (pintype "passive"))
    )
    (net (code "110") (name "/SDRAM_A10") (class "Default")
      (node (ref "U1") (pin "57") (pinfunction "SD_A10/__SRAM_A10_57") (pintype "passive"))
      (node (ref "U3") (pin "22") (pinfunction "A10_22") (pintype "passive"))
    )
    (net (code "111") (name "/SDRAM_A11") (class "Default")
      (node (ref "U1") (pin "56") (pinfunction "SD_A11/__SRAM_A11_56") (pintype "passive"))
      (node (ref "U3") (pin "35") (pinfunction "A11_35") (pintype "passive"))
    )
    (net (code "112") (name "/SDRAM_A12") (class "Default")
      (node (ref "U1") (pin "55") (pinfunction "SD_A12/__SRAM_A12_55") (pintype "passive"))
      (node (ref "U3") (pin "36") (pinfunction "NC_36") (pintype "passive"))
    )
    (net (code "113") (name "/SDRAM_BA0") (class "Default")
      (node (ref "U1") (pin "52") (pinfunction "SD_BA0/__SRAM_A17_52") (pintype "passive"))
      (node (ref "U3") (pin "20") (pinfunction "BA0_20") (pintype "passive"))
    )
    (net (code "114") (name "/SDRAM_BA1") (class "Default")
      (node (ref "U1") (pin "50") (pinfunction "SD_BA1/__SRAM_A16_50") (pintype "passive"))
      (node (ref "U3") (pin "21") (pinfunction "BA1_21") (pintype "passive"))
    )
    (net (code "115") (name "/SDRAM_CKE") (class "Default")
      (node (ref "U1") (pin "53") (pinfunction "SD_CKE/__SRAM_A13_53") (pintype "passive"))
      (node (ref "U3") (pin "37") (pinfunction "CKE_37") (pintype "passive"))
    )
    (net (code "116") (name "/SDRAM_CLK") (class "Default")
      (node (ref "U1") (pin "54") (pinfunction "SD_CLK/__SRAM_OEn_54") (pintype "passive"))
      (node (ref "U3") (pin "38") (pinfunction "CLK_38") (pintype "passive"))
    )
    (net (code "117") (name "/SDRAM_D0") (class "Default")
      (node (ref "U1") (pin "44") (pinfunction "SD_D00/__SRAM_D00_44") (pintype "passive"))
      (node (ref "U3") (pin "2") (pinfunction "I/O0_2") (pintype "passive"))
    )
    (net (code "118") (name "/SDRAM_D1") (class "Default")
      (node (ref "U1") (pin "43") (pinfunction "SD_D01/__SRAM_D01_43") (pintype "passive"))
      (node (ref "U3") (pin "4") (pinfunction "I/O1_4") (pintype "passive"))
    )
    (net (code "119") (name "/SDRAM_D2") (class "Default")
      (node (ref "U1") (pin "42") (pinfunction "SD_D02/__SRAM_D02_42") (pintype "passive"))
      (node (ref "U3") (pin "5") (pinfunction "I/O2_5") (pintype "passive"))
    )
    (net (code "120") (name "/SDRAM_D3") (class "Default")
      (node (ref "U1") (pin "41") (pinfunction "SD_D03/__SRAM_D03_41") (pintype "passive"))
      (node (ref "U3") (pin "7") (pinfunction "I/O3_7") (pintype "passive"))
    )
    (net (code "121") (name "/SDRAM_D4") (class "Default")
      (node (ref "U1") (pin "40") (pinfunction "SD_D04/__SRAM_D04_40") (pintype "passive"))
      (node (ref "U3") (pin "8") (pinfunction "I/O4_8") (pintype "passive"))
    )
    (net (code "122") (name "/SDRAM_D5") (class "Default")
      (node (ref "U1") (pin "39") (pinfunction "SD_D05/__SRAM_D05_39") (pintype "passive"))
      (node (ref "U3") (pin "10") (pinfunction "I/O5_10") (pintype "passive"))
    )
    (net (code "123") (name "/SDRAM_D6") (class "Default")
      (node (ref "U1") (pin "38") (pinfunction "SD_D06/__SRAM_D06_38") (pintype "passive"))
      (node (ref "U3") (pin "11") (pinfunction "I/O6_11") (pintype "passive"))
    )
    (net (code "124") (name "/SDRAM_D7") (class "Default")
      (node (ref "U1") (pin "37") (pinfunction "SD_D07/__SRAM_D07_37") (pintype "passive"))
      (node (ref "U3") (pin "13") (pinfunction "I/O7_13") (pintype "passive"))
    )
    (net (code "125") (name "/SDRAM_D8") (class "Default")
      (node (ref "U1") (pin "34") (pinfunction "SD_D08/__SRAM_D08_/GPIO97_/I2S_MCLK_/NAND_CLE_/I2C_SDA2_/CAN0_RX_34") (pintype "passive"))
      (node (ref "U3") (pin "42") (pinfunction "I/O8_42") (pintype "passive"))
    )
    (net (code "126") (name "/SDRAM_D9") (class "Default")
      (node (ref "U1") (pin "33") (pinfunction "SD_D09/__SRAM_D09_/GPIO98_/I2S_BCLK_/NAND_RD#_/I2C_SCL2_/CANO_TX_33") (pintype "passive"))
      (node (ref "U3") (pin "44") (pinfunction "I/O9_44") (pintype "passive"))
    )
    (net (code "127") (name "/SDRAM_D10") (class "Default")
      (node (ref "U1") (pin "32") (pinfunction "SD_D10/__SRAM_D10__/GPIO99_/I2S_DI_/NAND_ALE_/UART0_RX_/CAN1_RX_32") (pintype "passive"))
      (node (ref "U3") (pin "45") (pinfunction "I/O10_45") (pintype "passive"))
    )
    (net (code "128") (name "/SDRAM_D11") (class "Default")
      (node (ref "U1") (pin "31") (pinfunction "SD_D11/__SRAM_D11__/GPIO100_/I2S_LRCK_/NAND_WR#_/UART0_TX_/CAN1_TX_31") (pintype "passive"))
      (node (ref "U3") (pin "47") (pinfunction "I/O11_47") (pintype "passive"))
    )
    (net (code "129") (name "/SDRAM_D12") (class "Default")
      (node (ref "U1") (pin "30") (pinfunction "SD_D12/__SRAM_D13/_GPIO101_/UART1_RX_/NAND_RDY_/I2C_SDA1_/PWM0_30") (pintype "passive"))
      (node (ref "U3") (pin "48") (pinfunction "I/O12_48") (pintype "passive"))
    )
    (net (code "130") (name "/SDRAM_D13") (class "Default")
      (node (ref "U1") (pin "29") (pinfunction "SD_D13/__SRAM_D13__/GPIO102_/UART1_TX_/NAND_CE#_/I2C_SCL1_/PWM1_29") (pintype "passive"))
      (node (ref "U3") (pin "50") (pinfunction "I/O13_50") (pintype "passive"))
    )
    (net (code "131") (name "/SDRAM_D14") (class "Default")
      (node (ref "U1") (pin "28") (pinfunction "SD_D14/__SRAM_D14__/GPIO103_/I2C_SDA/_PWM2_/UART2_RX_/MDC_28") (pintype "passive"))
      (node (ref "U3") (pin "51") (pinfunction "I/O14_51") (pintype "passive"))
    )
    (net (code "132") (name "/SDRAM_D15") (class "Default")
      (node (ref "U1") (pin "27") (pinfunction "SD_D15/__SRAM_D15_/GPIO104_/I2C_SCL_/PWM3_/UART2_TX_/MDIO_27") (pintype "passive"))
      (node (ref "U3") (pin "53") (pinfunction "I/O15_53") (pintype "passive"))
    )
    (net (code "133") (name "/SDRAM_DQM0") (class "Default")
      (node (ref "U1") (pin "36") (pinfunction "SD_DQM0/__SRAM_BLEn_36") (pintype "passive"))
      (node (ref "U3") (pin "15") (pinfunction "LDQM_15") (pintype "passive"))
    )
    (net (code "134") (name "/SDRAM_DQM1") (class "Default")
      (node (ref "U1") (pin "35") (pinfunction "SD_DQM1/__SRAM_BHEn__/GPIO96_/I2S_DO_/PWM1_/XTALI_/UART6_RX/__UART0_DCD_35") (pintype "passive"))
      (node (ref "U3") (pin "39") (pinfunction "UDQM_39") (pintype "passive"))
    )
    (net (code "135") (name "/SPI0_CLK") (class "Default")
      (node (ref "P7") (pin "9") (pinfunction "9_9") (pintype "passive"))
      (node (ref "R17") (pin "1") (pinfunction "1_1") (pintype "passive"))
      (node (ref "U1") (pin "94") (pinfunction "SPI_CLK_/GPIO78_/Sdio_clk_/UART5_TX/__UART0_DTR_94") (pintype "passive"))
      (node (ref "U4") (pin "6") (pinfunction "CLK_6") (pintype "passive"))
    )
    (net (code "136") (name "/SPI0_CS0") (class "Default")
      (node (ref "P7") (pin "6") (pinfunction "6_6") (pintype "passive"))
      (node (ref "U1") (pin "92") (pinfunction "SPI0_CS0_/GPIO81_/Sdio_Dat1_/SDRAM_CS1_/UART5_RX/__UART0_DSR_92") (pintype "passive"))
    )
    (net (code "137") (name "/SPI0_MISO") (class "Default")
      (node (ref "P7") (pin "11") (pinfunction "11_11") (pintype "passive"))
      (node (ref "R19") (pin "1") (pinfunction "1_1") (pintype "passive"))
      (node (ref "U1") (pin "90") (pinfunction "SPI0_MISO_/GPIO80_/Sdio_Cmd_/UART4_RX/__UART0_CTS_90") (pintype "passive"))
      (node (ref "U4") (pin "2") (pinfunction "MISO_2") (pintype "passive"))
    )
    (net (code "138") (name "/SPI0_MOSI") (class "Default")
      (node (ref "P7") (pin "10") (pinfunction "10_10") (pintype "passive"))
      (node (ref "R18") (pin "1") (pinfunction "1_1") (pintype "passive"))
      (node (ref "U1") (pin "91") (pinfunction "SPI0_MOSI_/GPIO79_/Sdio_Dat0_/UART4_TX/__UART0_RTS_91") (pintype "passive"))
      (node (ref "U4") (pin "5") (pinfunction "MOSI_5") (pintype "passive"))
    )
    (net (code "139") (name "/UART2_RX") (class "Default")
      (node (ref "P2") (pin "15") (pinfunction "15_15") (pintype "passive"))
      (node (ref "U1") (pin "149") (pinfunction "MAC_COL_/GPIO36_/CAMDATA0_/UART2_RX_/LCD_R1_/SPI1_CS0/__Sdio_Dat1_149") (pintype "passive"))
      (node (ref "U6") (pin "5") (pinfunction "ERR#_5") (pintype "passive"))
    )
    (net (code "140") (name "/UART2_TX") (class "Default")
      (node (ref "P2") (pin "16") (pinfunction "16_16") (pintype "passive"))
      (node (ref "U1") (pin "150") (pinfunction "MAC_RXC_/GPIO37_/PWM3_/UART2_TX_/LCD_R2_/SPI1_CS1/__Sdio_Dat2_150") (pintype "passive"))
      (node (ref "U6") (pin "6") (pinfunction "PEMP_6") (pintype "passive"))
    )
    (net (code "141") (name "/XTALI") (class "Default")
      (node (ref "C1") (pin "2") (pinfunction "2_2") (pintype "passive"))
      (node (ref "R40") (pin "2") (pinfunction "2_2") (pintype "passive"))
      (node (ref "U1") (pin "1") (pinfunction "XTALI_1") (pintype "passive"))
      (node (ref "Y1") (pin "1") (pinfunction "OSC1_1") (pintype "passive"))
    )
    (net (code "142") (name "/XTALO") (class "Default")
      (node (ref "C2") (pin "2") (pinfunction "2_2") (pintype "passive"))
      (node (ref "R40") (pin "1") (pinfunction "1_1") (pintype "passive"))
      (node (ref "U1") (pin "2") (pinfunction "XTAL0_2") (pintype "passive"))
      (node (ref "Y1") (pin "2") (pinfunction "OSC2_2") (pintype "passive"))
    )
    (net (code "143") (name "/~{CH_CS}") (class "Default")
      (node (ref "P7") (pin "5") (pinfunction "5_5") (pintype "passive"))
      (node (ref "U6") (pin "15") (pinfunction "D0_15") (pintype "bidirectional"))
    )
    (net (code "144") (name "/~{SDRAM_CAS}") (class "Default")
      (node (ref "R23") (pin "2") (pinfunction "2_2") (pintype "passive"))
      (node (ref "U1") (pin "47") (pinfunction "SD_CASn/__SRAM_A15_47") (pintype "passive"))
      (node (ref "U3") (pin "17") (pinfunction "~{CAS}_17") (pintype "passive"))
    )
    (net (code "145") (name "/~{SDRAM_CS}") (class "Default")
      (node (ref "R21") (pin "2") (pinfunction "2_2") (pintype "passive"))
      (node (ref "U1") (pin "49") (pinfunction "SD_CSn/__SRAM_CSn_49") (pintype "passive"))
      (node (ref "U3") (pin "19") (pinfunction "~{CS}_19") (pintype "passive"))
    )
    (net (code "146") (name "/~{SDRAM_RAS}") (class "Default")
      (node (ref "R22") (pin "2") (pinfunction "2_2") (pintype "passive"))
      (node (ref "U1") (pin "48") (pinfunction "SD_RASn/__SRAM_A14_48") (pintype "passive"))
      (node (ref "U3") (pin "18") (pinfunction "~{RAS}_18") (pintype "passive"))
    )
    (net (code "147") (name "/~{SDRAM_WE}") (class "Default")
      (node (ref "R24") (pin "2") (pinfunction "2_2") (pintype "passive"))
      (node (ref "U1") (pin "46") (pinfunction "SD_WEn/__SRAM_WEn_46") (pintype "passive"))
      (node (ref "U3") (pin "16") (pinfunction "~{WE}_16") (pintype "passive"))
    )
    (net (code "148") (name "/~{SPI_HOLD}") (class "Default")
      (node (ref "R5") (pin "2") (pinfunction "2_2") (pintype "passive"))
      (node (ref "U4") (pin "7") (pinfunction "~{HOLD}_7") (pintype "passive"))
    )
    (net (code "149") (name "/~{SPI_WP}") (class "Default")
      (node (ref "R7") (pin "2") (pinfunction "2_2") (pintype "passive"))
      (node (ref "U4") (pin "3") (pinfunction "~{WP}_3") (pintype "passive"))
    )
    (net (code "150") (name "/~{SYS_RESET}") (class "Default")
      (node (ref "C32") (pin "2") (pinfunction "2_2") (pintype "passive"))
      (node (ref "P5") (pin "6") (pinfunction "RST_N_6") (pintype "passive"))
      (node (ref "R9") (pin "1") (pinfunction "1_1") (pintype "passive"))
      (node (ref "U1") (pin "125") (pinfunction "~{SYS_RST}_125") (pintype "passive"))
      (node (ref "U2") (pin "2") (pinfunction "~{RESET}_2") (pintype "passive"))
    )
    (net (code "151") (name "1V2") (class "Default")
      (node (ref "C20") (pin "2") (pinfunction "2_2") (pintype "passive"))
      (node (ref "C21") (pin "2") (pinfunction "2_2") (pintype "passive"))
      (node (ref "C22") (pin "2") (pinfunction "2_2") (pintype "passive"))
      (node (ref "C23") (pin "2") (pinfunction "2_2") (pintype "passive"))
      (node (ref "C24") (pin "2") (pinfunction "2_2") (pintype "passive"))
      (node (ref "C25") (pin "2") (pinfunction "2_2") (pintype "passive"))
      (node (ref "C26") (pin "2") (pinfunction "2_2") (pintype "passive"))
      (node (ref "C27") (pin "2") (pinfunction "2_2") (pintype "passive"))
      (node (ref "C28") (pin "2") (pinfunction "2_2") (pintype "passive"))
      (node (ref "C29") (pin "2") (pinfunction "2_2") (pintype "passive"))
      (node (ref "C30") (pin "2") (pinfunction "2_2") (pintype "passive"))
      (node (ref "C31") (pin "2") (pinfunction "2_2") (pintype "passive"))
      (node (ref "C60") (pin "1") (pinfunction "1_1") (pintype "passive"))
      (node (ref "C61") (pin "1") (pinfunction "1_1") (pintype "passive"))
      (node (ref "C62") (pin "2") (pinfunction "2_2") (pintype "passive"))
      (node (ref "L2") (pin "1") (pinfunction "1_1") (pintype "passive"))
      (node (ref "R13") (pin "2") (pinfunction "2_2") (pintype "passive"))
      (node (ref "U1") (pin "101") (pinfunction "CORE_VDD_101") (pintype "passive"))
      (node (ref "U1") (pin "11") (pinfunction "CORE_VDD_11") (pintype "passive"))
      (node (ref "U1") (pin "124") (pinfunction "CORE_VDD_124") (pintype "passive"))
      (node (ref "U1") (pin "152") (pinfunction "CORE_VDD_152") (pintype "passive"))
      (node (ref "U1") (pin "154") (pinfunction "OTG_DVDD_154") (pintype "passive"))
      (node (ref "U1") (pin "164") (pinfunction "USB_DVDD_164") (pintype "passive"))
      (node (ref "U1") (pin "171") (pinfunction "PLL_VDD12_171") (pintype "passive"))
      (node (ref "U1") (pin "26") (pinfunction "CORE_VDD_26") (pintype "passive"))
      (node (ref "U1") (pin "68") (pinfunction "CORE_VDD_68") (pintype "passive"))
    )
    (net (code "152") (name "3V3") (class "Default")
      (node (ref "C10") (pin "2") (pinfunction "2_2") (pintype "passive"))
      (node (ref "C11") (pin "2") (pinfunction "2_2") (pintype "passive"))
      (node (ref "C12") (pin "2") (pinfunction "2_2") (pintype "passive"))
      (node (ref "C13") (pin "2") (pinfunction "2_2") (pintype "passive"))
      (node (ref "C14") (pin "2") (pinfunction "2_2") (pintype "passive"))
      (node (ref "C15") (pin "2") (pinfunction "2_2") (pintype "passive"))
      (node (ref "C16") (pin "2") (pinfunction "2_2") (pintype "passive"))
      (node (ref "C17") (pin "2") (pinfunction "2_2") (pintype "passive"))
      (node (ref "C37") (pin "2") (pinfunction "2_2") (pintype "passive"))
      (node (ref "C38") (pin "2") (pinfunction "2_2") (pintype "passive"))
      (node (ref "C39") (pin "2") (pinfunction "2_2") (pintype "passive"))
      (node (ref "C40") (pin "2") (pinfunction "2_2") (pintype "passive"))
      (node (ref "C41") (pin "2") (pinfunction "2_2") (pintype "passive"))
      (node (ref "C42") (pin "2") (pinfunction "2_2") (pintype "passive"))
      (node (ref "C43") (pin "2") (pinfunction "2_2") (pintype "passive"))
      (node (ref "C44") (pin "2") (pinfunction "2_2") (pintype "passive"))
      (node (ref "C45") (pin "2") (pinfunction "2_2") (pintype "passive"))
      (node (ref "C46") (pin "2") (pinfunction "2_2") (pintype "passive"))
      (node (ref "C47") (pin "2") (pinfunction "2_2") (pintype "passive"))
      (node (ref "C48") (pin "2") (pinfunction "2_2") (pintype "passive"))
      (node (ref "C5") (pin "2") (pinfunction "2_2") (pintype "passive"))
      (node (ref "C52") (pin "2") (pinfunction "2_2") (pintype "passive"))
      (node (ref "C56") (pin "2") (pinfunction "2_2") (pintype "passive"))
      (node (ref "C57") (pin "2") (pinfunction "2_2") (pintype "passive"))
      (node (ref "C58") (pin "2") (pinfunction "2_2") (pintype "passive"))
      (node (ref "C59") (pin "2") (pinfunction "2_2") (pintype "passive"))
      (node (ref "C6") (pin "2") (pinfunction "2_2") (pintype "passive"))
      (node (ref "C67") (pin "1") (pinfunction "1_1") (pintype "passive"))
      (node (ref "C68") (pin "1") (pinfunction "1_1") (pintype "passive"))
      (node (ref "C69") (pin "2") (pinfunction "2_2") (pintype "passive"))
      (node (ref "C7") (pin "2") (pinfunction "2_2") (pintype "passive"))
      (node (ref "C8") (pin "2") (pinfunction "2_2") (pintype "passive"))
      (node (ref "C9") (pin "2") (pinfunction "2_2") (pintype "passive"))
      (node (ref "D1") (pin "1") (pinfunction "A_1") (pintype "passive"))
      (node (ref "L1") (pin "1") (pinfunction "1_1") (pintype "passive"))
      (node (ref "L3") (pin "1") (pinfunction "1_1") (pintype "passive"))
      (node (ref "P1") (pin "27") (pinfunction "27_27") (pintype "passive"))
      (node (ref "P1") (pin "28") (pinfunction "28_28") (pintype "passive"))
      (node (ref "P5") (pin "8") (pinfunction "3V3_8") (pintype "passive"))
      (node (ref "R1") (pin "2") (pinfunction "2_2") (pintype "passive"))
      (node (ref "R15") (pin "1") (pinfunction "1_1") (pintype "passive"))
      (node (ref "R17") (pin "2") (pinfunction "2_2") (pintype "passive"))
      (node (ref "R18") (pin "2") (pinfunction "2_2") (pintype "passive"))
      (node (ref "R19") (pin "2") (pinfunction "2_2") (pintype "passive"))
      (node (ref "R21") (pin "1") (pinfunction "1_1") (pintype "passive"))
      (node (ref "R22") (pin "1") (pinfunction "1_1") (pintype "passive"))
      (node (ref "R23") (pin "1") (pinfunction "1_1") (pintype "passive"))
      (node (ref "R24") (pin "1") (pinfunction "1_1") (pintype "passive"))
      (node (ref "R28") (pin "2") (pinfunction "2_2") (pintype "passive"))
      (node (ref "R3") (pin "2") (pinfunction "2_2") (pintype "passive"))
      (node (ref "R30") (pin "2") (pinfunction "2_2") (pintype "passive"))
      (node (ref "R31") (pin "2") (pinfunction "2_2") (pintype "passive"))
      (node (ref "R32") (pin "2") (pinfunction "2_2") (pintype "passive"))
      (node (ref "R33") (pin "2") (pinfunction "2_2") (pintype "passive"))
      (node (ref "R34") (pin "2") (pinfunction "2_2") (pintype "passive"))
      (node (ref "R36") (pin "2") (pinfunction "2_2") (pintype "passive"))
      (node (ref "R38") (pin "2") (pinfunction "2_2") (pintype "passive"))
      (node (ref "R5") (pin "1") (pinfunction "1_1") (pintype "passive"))
      (node (ref "R6") (pin "1") (pinfunction "1_1") (pintype "passive"))
      (node (ref "R7") (pin "1") (pinfunction "1_1") (pintype "passive"))
      (node (ref "R9") (pin "2") (pinfunction "2_2") (pintype "passive"))
      (node (ref "S1") (pin "1") (pinfunction "1_1") (pintype "passive"))
      (node (ref "U1") (pin "102") (pinfunction "IO_VDD_102") (pintype "passive"))
      (node (ref "U1") (pin "131") (pinfunction "IO_VDD_131") (pintype "passive"))
      (node (ref "U1") (pin "155") (pinfunction "OTG_VDD33_155") (pintype "passive"))
      (node (ref "U1") (pin "165") (pinfunction "USB_VDD33_165") (pintype "passive"))
      (node (ref "U1") (pin "173") (pinfunction "PLL_VDD33_173") (pintype "passive"))
      (node (ref "U1") (pin "18") (pinfunction "IO_VDD_18") (pintype "passive"))
      (node (ref "U1") (pin "45") (pinfunction "IO_VDD_45") (pintype "passive"))
      (node (ref "U1") (pin "69") (pinfunction "IO_VDD_69") (pintype "passive"))
      (node (ref "U2") (pin "4") (pinfunction "VCC_4") (pintype "passive"))
      (node (ref "U3") (pin "1") (pinfunction "VCC_1") (pintype "passive"))
      (node (ref "U3") (pin "14") (pinfunction "VCC_14") (pintype "passive"))
      (node (ref "U3") (pin "27") (pinfunction "VCC_27") (pintype "passive"))
      (node (ref "U3") (pin "3") (pinfunction "VCCQ_3") (pintype "passive"))
      (node (ref "U3") (pin "43") (pinfunction "VCCQ_43") (pintype "passive"))
      (node (ref "U3") (pin "49") (pinfunction "VCCQ_49") (pintype "passive"))
      (node (ref "U3") (pin "9") (pinfunction "VCCQ_9") (pintype "passive"))
      (node (ref "U4") (pin "8") (pinfunction "VCC_8") (pintype "passive"))
      (node (ref "U6") (pin "28") (pinfunction "VCC_28") (pintype "power_in"))
      (node (ref "U6") (pin "9") (pinfunction "V3_9") (pintype "power_in"))
    )
    (net (code "153") (name "5V") (class "Default")
      (node (ref "C36") (pin "1") (pinfunction "1_1") (pintype "passive"))
      (node (ref "C53") (pin "1") (pinfunction "1_1") (pintype "passive"))
      (node (ref "C54") (pin "2") (pinfunction "2_2") (pintype "passive"))
      (node (ref "C65") (pin "2") (pinfunction "2_2") (pintype "passive"))
      (node (ref "F1") (pin "1") (pinfunction "1_1") (pintype "passive"))
      (node (ref "R10") (pin "1") (pinfunction "1_1") (pintype "passive"))
      (node (ref "R25") (pin "1") (pinfunction "1_1") (pintype "passive"))
      (node (ref "U5") (pin "2") (pinfunction "IN_2") (pintype "passive"))
      (node (ref "U8") (pin "2") (pinfunction "IN_2") (pintype "passive"))
    )
    (net (code "154") (name "5V1") (class "Default")
      (node (ref "F1") (pin "2") (pinfunction "2_2") (pintype "passive"))
      (node (ref "P1") (pin "1") (pinfunction "1_1") (pintype "passive"))
      (node (ref "P2") (pin "1") (pinfunction "1_1") (pintype "passive"))
      (node (ref "U7") (pin "1") (pinfunction "+5V_1") (pintype "power_in"))
    )
    (net (code "155") (name "ADC_VDDA") (class "Default")
      (node (ref "C18") (pin "2") (pinfunction "2_2") (pintype "passive"))
      (node (ref "C19") (pin "2") (pinfunction "2_2") (pintype "passive"))
      (node (ref "L1") (pin "2") (pinfunction "2_2") (pintype "passive"))
      (node (ref "U1") (pin "83") (pinfunction "ADC_VDDA_83") (pintype "passive"))
    )
    (net (code "156") (name "GND") (class "Default")
      (node (ref "C1") (pin "1") (pinfunction "1_1") (pintype "passive"))
      (node (ref "C10") (pin "1") (pinfunction "1_1") (pintype "passive"))
      (node (ref "C11") (pin "1") (pinfunction "1_1") (pintype "passive"))
      (node (ref "C12") (pin "1") (pinfunction "1_1") (pintype "passive"))
      (node (ref "C13") (pin "1") (pinfunction "1_1") (pintype "passive"))
      (node (ref "C14") (pin "1") (pinfunction "1_1") (pintype "passive"))
      (node (ref "C15") (pin "1") (pinfunction "1_1") (pintype "passive"))
      (node (ref "C16") (pin "1") (pinfunction "1_1") (pintype "passive"))
      (node (ref "C17") (pin "1") (pinfunction "1_1") (pintype "passive"))
      (node (ref "C18") (pin "1") (pinfunction "1_1") (pintype "passive"))
      (node (ref "C19") (pin "1") (pinfunction "1_1") (pintype "passive"))
      (node (ref "C2") (pin "1") (pinfunction "1_1") (pintype "passive"))
      (node (ref "C20") (pin "1") (pinfunction "1_1") (pintype "passive"))
      (node (ref "C21") (pin "1") (pinfunction "1_1") (pintype "passive"))
      (node (ref "C22") (pin "1") (pinfunction "1_1") (pintype "passive"))
      (node (ref "C23") (pin "1") (pinfunction "1_1") (pintype "passive"))
      (node (ref "C24") (pin "1") (pinfunction "1_1") (pintype "passive"))
      (node (ref "C25") (pin "1") (pinfunction "1_1") (pintype "passive"))
      (node (ref "C26") (pin "1") (pinfunction "1_1") (pintype "passive"))
      (node (ref "C27") (pin "1") (pinfunction "1_1") (pintype "passive"))
      (node (ref "C28") (pin "1") (pinfunction "1_1") (pintype "passive"))
      (node (ref "C29") (pin "1") (pinfunction "1_1") (pintype "passive"))
      (node (ref "C3") (pin "1") (pinfunction "1_1") (pintype "passive"))
      (node (ref "C30") (pin "1") (pinfunction "1_1") (pintype "passive"))
      (node (ref "C31") (pin "1") (pinfunction "1_1") (pintype "passive"))
      (node (ref "C32") (pin "1") (pinfunction "1_1") (pintype "passive"))
      (node (ref "C33") (pin "2") (pinfunction "2_2") (pintype "passive"))
      (node (ref "C36") (pin "2") (pinfunction "2_2") (pintype "passive"))
      (node (ref "C37") (pin "1") (pinfunction "1_1") (pintype "passive"))
      (node (ref "C38") (pin "1") (pinfunction "1_1") (pintype "passive"))
      (node (ref "C39") (pin "1") (pinfunction "1_1") (pintype "passive"))
      (node (ref "C4") (pin "1") (pinfunction "1_1") (pintype "passive"))
      (node (ref "C40") (pin "1") (pinfunction "1_1") (pintype "passive"))
      (node (ref "C41") (pin "1") (pinfunction "1_1") (pintype "passive"))
      (node (ref "C42") (pin "1") (pinfunction "1_1") (pintype "passive"))
      (node (ref "C43") (pin "1") (pinfunction "1_1") (pintype "passive"))
      (node (ref "C44") (pin "1") (pinfunction "1_1") (pintype "passive"))
      (node (ref "C45") (pin "1") (pinfunction "1_1") (pintype "passive"))
      (node (ref "C46") (pin "1") (pinfunction "1_1") (pintype "passive"))
      (node (ref "C47") (pin "1") (pinfunction "1_1") (pintype "passive"))
      (node (ref "C48") (pin "1") (pinfunction "1_1") (pintype "passive"))
      (node (ref "C49") (pin "2") (pinfunction "2_2") (pintype "passive"))
      (node (ref "C5") (pin "1") (pinfunction "1_1") (pintype "passive"))
      (node (ref "C53") (pin "2") (pinfunction "2_2") (pintype "passive"))
      (node (ref "C54") (pin "1") (pinfunction "1_1") (pintype "passive"))
      (node (ref "C56") (pin "1") (pinfunction "1_1") (pintype "passive"))
      (node (ref "C57") (pin "1") (pinfunction "1_1") (pintype "passive"))
      (node (ref "C58") (pin "1") (pinfunction "1_1") (pintype "passive"))
      (node (ref "C59") (pin "1") (pinfunction "1_1") (pintype "passive"))
      (node (ref "C6") (pin "1") (pinfunction "1_1") (pintype "passive"))
      (node (ref "C60") (pin "2") (pinfunction "2_2") (pintype "passive"))
      (node (ref "C61") (pin "2") (pinfunction "2_2") (pintype "passive"))
      (node (ref "C62") (pin "1") (pinfunction "1_1") (pintype "passive"))
      (node (ref "C63") (pin "1") (pinfunction "1_1") (pintype "passive"))
      (node (ref "C64") (pin "1") (pinfunction "1_1") (pintype "passive"))
      (node (ref "C65") (pin "1") (pinfunction "1_1") (pintype "passive"))
      (node (ref "C67") (pin "2") (pinfunction "2_2") (pintype "passive"))
      (node (ref "C68") (pin "2") (pinfunction "2_2") (pintype "passive"))
      (node (ref "C69") (pin "1") (pinfunction "1_1") (pintype "passive"))
      (node (ref "C7") (pin "1") (pinfunction "1_1") (pintype "passive"))
      (node (ref "C8") (pin "1") (pinfunction "1_1") (pintype "passive"))
      (node (ref "C9") (pin "1") (pinfunction "1_1") (pintype "passive"))
      (node (ref "D2") (pin "1") (pinfunction "A_1") (pintype "passive"))
      (node (ref "D4") (pin "1") (pinfunction "A_1") (pintype "passive"))
      (node (ref "D5") (pin "2") (pinfunction "K_2") (pintype "passive"))
      (node (ref "P1") (pin "11") (pinfunction "11_11") (pintype "passive"))
      (node (ref "P1") (pin "18") (pinfunction "18_18") (pintype "passive"))
      (node (ref "P1") (pin "2") (pinfunction "2_2") (pintype "passive"))
      (node (ref "P1") (pin "25") (pinfunction "25_25") (pintype "passive"))
      (node (ref "P1") (pin "26") (pinfunction "26_26") (pintype "passive"))
      (node (ref "P2") (pin "12") (pinfunction "12_12") (pintype "passive"))
      (node (ref "P2") (pin "14") (pinfunction "14_14") (pintype "passive"))
      (node (ref "P2") (pin "2") (pinfunction "2_2") (pintype "passive"))
      (node (ref "P2") (pin "24") (pinfunction "24_24") (pintype "passive"))
      (node (ref "P2") (pin "5") (pinfunction "5_5") (pintype "passive"))
      (node (ref "P2") (pin "9") (pinfunction "9_9") (pintype "passive"))
      (node (ref "P3") (pin "11") (pinfunction "11_11") (pintype "passive"))
      (node (ref "P3") (pin "12") (pinfunction "12_12") (pintype "passive"))
      (node (ref "P3") (pin "14") (pinfunction "14_14") (pintype "passive"))
      (node (ref "P3") (pin "5") (pinfunction "5_5") (pintype "passive"))
      (node (ref "P4") (pin "1") (pinfunction "1_1") (pintype "passive"))
      (node (ref "P4") (pin "12") (pinfunction "12_12") (pintype "passive"))
      (node (ref "P4") (pin "13") (pinfunction "13_13") (pintype "passive"))
      (node (ref "P4") (pin "21") (pinfunction "21_21") (pintype "passive"))
      (node (ref "P4") (pin "22") (pinfunction "22_22") (pintype "passive"))
      (node (ref "P5") (pin "10") (pinfunction "GND_10") (pintype "passive"))
      (node (ref "P5") (pin "11") (pinfunction "GND_11") (pintype "passive"))
      (node (ref "P5") (pin "12") (pinfunction "GND_12") (pintype "passive"))
      (node (ref "P5") (pin "13") (pinfunction "GND_13") (pintype "passive"))
      (node (ref "P5") (pin "14") (pinfunction "GND_14") (pintype "passive"))
      (node (ref "P6") (pin "11") (pinfunction "11_11") (pintype "passive"))
      (node (ref "P7") (pin "12") (pinfunction "12_12") (pintype "passive"))
      (node (ref "R11") (pin "1") (pinfunction "1_1") (pintype "passive"))
      (node (ref "R12") (pin "2") (pinfunction "2_2") (pintype "passive"))
      (node (ref "R14") (pin "1") (pinfunction "1_1") (pintype "passive"))
      (node (ref "R16") (pin "1") (pinfunction "1_1") (pintype "passive"))
      (node (ref "R2") (pin "1") (pinfunction "1_1") (pintype "passive"))
      (node (ref "R20") (pin "1") (pinfunction "1_1") (pintype "passive"))
      (node (ref "R26") (pin "1") (pinfunction "1_1") (pintype "passive"))
      (node (ref "R27") (pin "2") (pinfunction "2_2") (pintype "passive"))
      (node (ref "R29") (pin "1") (pinfunction "1_1") (pintype "passive"))
      (node (ref "R35") (pin "2") (pinfunction "2_2") (pintype "passive"))
      (node (ref "R37") (pin "2") (pinfunction "2_2") (pintype "passive"))
      (node (ref "R39") (pin "2") (pinfunction "2_2") (pintype "passive"))
      (node (ref "R4") (pin "1") (pinfunction "1_1") (pintype "passive"))
      (node (ref "R8") (pin "2") (pinfunction "2_2") (pintype "passive"))
      (node (ref "S2") (pin "1") (pinfunction "1_1") (pintype "passive"))
      (node (ref "U1") (pin "111") (pinfunction "CORE_VSS_111") (pintype "passive"))
      (node (ref "U1") (pin "142") (pinfunction "CORE_VSS_142") (pintype "passive"))
      (node (ref "U1") (pin "153") (pinfunction "OTG_DVSS_153") (pintype "passive"))
      (node (ref "U1") (pin "156") (pinfunction "OTG_VSS33_156") (pintype "passive"))
      (node (ref "U1") (pin "162") (pinfunction "CORE_VSS_162") (pintype "passive"))
      (node (ref "U1") (pin "163") (pinfunction "USB_DVSS_163") (pintype "passive"))
      (node (ref "U1") (pin "166") (pinfunction "USB_VSS33_166") (pintype "passive"))
      (node (ref "U1") (pin "170") (pinfunction "PLL_VSS12_170") (pintype "passive"))
      (node (ref "U1") (pin "172") (pinfunction "PLL_VSS33_172") (pintype "passive"))
      (node (ref "U1") (pin "22") (pinfunction "CORE_VSS_22") (pintype "passive"))
      (node (ref "U1") (pin "51") (pinfunction "CORE_VSS_51") (pintype "passive"))
      (node (ref "U1") (pin "80") (pinfunction "CORE_VSS_80") (pintype "passive"))
      (node (ref "U1") (pin "84") (pinfunction "ADC_VSSA_84") (pintype "passive"))
      (node (ref "U2") (pin "1") (pinfunction "GND_1") (pintype "passive"))
      (node (ref "U3") (pin "12") (pinfunction "GNDQ_12") (pintype "passive"))
      (node (ref "U3") (pin "28") (pinfunction "GND_28") (pintype "passive"))
      (node (ref "U3") (pin "41") (pinfunction "GND_41") (pintype "passive"))
      (node (ref "U3") (pin "46") (pinfunction "GNDQ_46") (pintype "passive"))
      (node (ref "U3") (pin "52") (pinfunction "GNDQ_52") (pintype "passive"))
      (node (ref "U3") (pin "54") (pinfunction "GND_54") (pintype "passive"))
      (node (ref "U3") (pin "6") (pinfunction "GNDQ_6") (pintype "passive"))
      (node (ref "U4") (pin "4") (pinfunction "GND_4") (pintype "passive"))
      (node (ref "U5") (pin "4") (pinfunction "GND_4") (pintype "passive"))
      (node (ref "U6") (pin "12") (pinfunction "GND_12") (pintype "power_in"))
      (node (ref "U6") (pin "27") (pinfunction "BUSY_27") (pintype "input"))
      (node (ref "U7") (pin "4") (pinfunction "GND_4") (pintype "power_in"))
      (node (ref "U7") (pin "5") (pinfunction "GND_5") (pintype "power_in"))
      (node (ref "U7") (pin "6") (pinfunction "GND_6") (pintype "power_in"))
      (node (ref "U8") (pin "4") (pinfunction "GND_4") (pintype "passive"))
    )
    (net (code "157") (name "Net-(C35-Pad1)") (class "Default")
      (node (ref "C35") (pin "1") (pinfunction "1_1") (pintype "passive"))
      (node (ref "R26") (pin "2") (pinfunction "2_2") (pintype "passive"))
    )
    (net (code "158") (name "Net-(C51-Pad1)") (class "Default")
      (node (ref "C51") (pin "1") (pinfunction "1_1") (pintype "passive"))
      (node (ref "R11") (pin "2") (pinfunction "2_2") (pintype "passive"))
    )
    (net (code "159") (name "Net-(C55-Pad1)") (class "Default")
      (node (ref "C55") (pin "1") (pinfunction "1_1") (pintype "passive"))
      (node (ref "R12") (pin "1") (pinfunction "1_1") (pintype "passive"))
    )
    (net (code "160") (name "Net-(C66-Pad1)") (class "Default")
      (node (ref "C66") (pin "1") (pinfunction "1_1") (pintype "passive"))
      (node (ref "R27") (pin "1") (pinfunction "1_1") (pintype "passive"))
    )
    (net (code "161") (name "Net-(D2-K)") (class "Default")
      (node (ref "C34") (pin "2") (pinfunction "2_2") (pintype "passive"))
      (node (ref "C66") (pin "2") (pinfunction "2_2") (pintype "passive"))
      (node (ref "D2") (pin "2") (pinfunction "K_2") (pintype "passive"))
      (node (ref "L3") (pin "2") (pinfunction "2_2") (pintype "passive"))
      (node (ref "U8") (pin "3") (pinfunction "SW_3") (pintype "passive"))
    )
    (net (code "162") (name "Net-(D3-A)") (class "Default")
      (node (ref "D3") (pin "1") (pinfunction "A_1") (pintype "passive"))
      (node (ref "R3") (pin "1") (pinfunction "1_1") (pintype "passive"))
    )
    (net (code "163") (name "Net-(D4-K)") (class "Default")
      (node (ref "C50") (pin "2") (pinfunction "2_2") (pintype "passive"))
      (node (ref "C55") (pin "2") (pinfunction "2_2") (pintype "passive"))
      (node (ref "D4") (pin "2") (pinfunction "K_2") (pintype "passive"))
      (node (ref "L2") (pin "2") (pinfunction "2_2") (pintype "passive"))
      (node (ref "U5") (pin "3") (pinfunction "SW_3") (pintype "passive"))
    )
    (net (code "164") (name "Net-(D5-A)") (class "Default")
      (node (ref "D5") (pin "1") (pinfunction "A_1") (pintype "passive"))
      (node (ref "R1") (pin "1") (pinfunction "1_1") (pintype "passive"))
    )
    (net (code "165") (name "Net-(U1-ADC_REXT)") (class "Default")
      (node (ref "R20") (pin "2") (pinfunction "2_2") (pintype "passive"))
      (node (ref "U1") (pin "81") (pinfunction "ADC_REXT_81") (pintype "passive"))
    )
    (net (code "166") (name "Net-(U1-OTG_REXT)") (class "Default")
      (node (ref "R4") (pin "2") (pinfunction "2_2") (pintype "passive"))
      (node (ref "U1") (pin "159") (pinfunction "OTG_REXT_159") (pintype "passive"))
    )
    (net (code "167") (name "Net-(U1-USB_REXT)") (class "Default")
      (node (ref "R2") (pin "2") (pinfunction "2_2") (pintype "passive"))
      (node (ref "U1") (pin "167") (pinfunction "USB_REXT_167") (pintype "passive"))
    )
    (net (code "168") (name "Net-(U2-~{MR})") (class "Default")
      (node (ref "S2") (pin "2") (pinfunction "2_2") (pintype "passive"))
      (node (ref "U2") (pin "3") (pinfunction "~{MR}_3") (pintype "passive"))
    )
    (net (code "169") (name "Net-(U5-BS)") (class "Default")
      (node (ref "C50") (pin "1") (pinfunction "1_1") (pintype "passive"))
      (node (ref "U5") (pin "1") (pinfunction "BS_1") (pintype "passive"))
    )
    (net (code "170") (name "Net-(U5-COMP)") (class "Default")
      (node (ref "C51") (pin "2") (pinfunction "2_2") (pintype "passive"))
      (node (ref "U5") (pin "6") (pinfunction "COMP_6") (pintype "passive"))
    )
    (net (code "171") (name "Net-(U5-EN)") (class "Default")
      (node (ref "R10") (pin "2") (pinfunction "2_2") (pintype "passive"))
      (node (ref "U5") (pin "7") (pinfunction "EN_7") (pintype "passive"))
    )
    (net (code "172") (name "Net-(U5-FB)") (class "Default")
      (node (ref "R13") (pin "1") (pinfunction "1_1") (pintype "passive"))
      (node (ref "R14") (pin "2") (pinfunction "2_2") (pintype "passive"))
      (node (ref "U5") (pin "5") (pinfunction "FB_5") (pintype "passive"))
    )
    (net (code "173") (name "Net-(U5-SS)") (class "Default")
      (node (ref "C49") (pin "1") (pinfunction "1_1") (pintype "passive"))
      (node (ref "U5") (pin "8") (pinfunction "SS_8") (pintype "passive"))
    )
    (net (code "174") (name "Net-(U6-RSTI)") (class "Default")
      (node (ref "C52") (pin "1") (pinfunction "1_1") (pintype "passive"))
      (node (ref "R8") (pin "1") (pinfunction "1_1") (pintype "passive"))
      (node (ref "S1") (pin "2") (pinfunction "2_2") (pintype "passive"))
      (node (ref "U6") (pin "2") (pinfunction "RSTI_2") (pintype "passive"))
    )
    (net (code "175") (name "Net-(U6-UD+)") (class "Default")
      (node (ref "U6") (pin "10") (pinfunction "UD+_10") (pintype "bidirectional"))
      (node (ref "U7") (pin "3") (pinfunction "UD+_3") (pintype "bidirectional"))
    )
    (net (code "176") (name "Net-(U6-UD-)") (class "Default")
      (node (ref "U6") (pin "11") (pinfunction "UD-_11") (pintype "bidirectional"))
      (node (ref "U7") (pin "2") (pinfunction "UD-_2") (pintype "bidirectional"))
    )
    (net (code "177") (name "Net-(U6-XI)") (class "Default")
      (node (ref "C63") (pin "2") (pinfunction "2_2") (pintype "passive"))
      (node (ref "U6") (pin "13") (pinfunction "XI_13") (pintype "passive"))
      (node (ref "Y3") (pin "1") (pinfunction "1_1") (pintype "passive"))
    )
    (net (code "178") (name "Net-(U6-XO)") (class "Default")
      (node (ref "C64") (pin "2") (pinfunction "2_2") (pintype "passive"))
      (node (ref "U6") (pin "14") (pinfunction "XO_14") (pintype "output"))
      (node (ref "Y3") (pin "2") (pinfunction "2_2") (pintype "passive"))
    )
    (net (code "179") (name "Net-(U8-BS)") (class "Default")
      (node (ref "C34") (pin "1") (pinfunction "1_1") (pintype "passive"))
      (node (ref "U8") (pin "1") (pinfunction "BS_1") (pintype "passive"))
    )
    (net (code "180") (name "Net-(U8-COMP)") (class "Default")
      (node (ref "C35") (pin "2") (pinfunction "2_2") (pintype "passive"))
      (node (ref "U8") (pin "6") (pinfunction "COMP_6") (pintype "passive"))
    )
    (net (code "181") (name "Net-(U8-EN)") (class "Default")
      (node (ref "R25") (pin "2") (pinfunction "2_2") (pintype "passive"))
      (node (ref "U8") (pin "7") (pinfunction "EN_7") (pintype "passive"))
    )
    (net (code "182") (name "Net-(U8-FB)") (class "Default")
      (node (ref "R28") (pin "1") (pinfunction "1_1") (pintype "passive"))
      (node (ref "R29") (pin "2") (pinfunction "2_2") (pintype "passive"))
      (node (ref "U8") (pin "5") (pinfunction "FB_5") (pintype "passive"))
    )
    (net (code "183") (name "Net-(U8-SS)") (class "Default")
      (node (ref "C33") (pin "1") (pinfunction "1_1") (pintype "passive"))
      (node (ref "U8") (pin "8") (pinfunction "SS_8") (pintype "passive"))
    )
    (net (code "184") (name "unconnected-(P5-NC-Pad7)") (class "Default")
      (node (ref "P5") (pin "7") (pinfunction "NC_7") (pintype "passive"))
    )
    (net (code "185") (name "unconnected-(P5-NC-Pad9)") (class "Default")
      (node (ref "P5") (pin "9") (pinfunction "NC_9") (pintype "passive"))
    )
    (net (code "186") (name "unconnected-(U3-NC-Pad40)") (class "Default")
      (node (ref "U3") (pin "40") (pinfunction "NC_40") (pintype "passive"))
    )
    (net (code "187") (name "unconnected-(U6-ACK#-Pad7)") (class "Default")
      (node (ref "U6") (pin "7") (pinfunction "ACK#_7") (pintype "passive"))
    )
    (net (code "188") (name "unconnected-(U6-ACT#-Pad1)") (class "Default")
      (node (ref "U6") (pin "1") (pinfunction "ACT#_1") (pintype "output"))
    )
    (net (code "189") (name "unconnected-(U6-AFD#-Pad4)") (class "Default")
      (node (ref "U6") (pin "4") (pinfunction "AFD#_4") (pintype "output"))
    )
    (net (code "190") (name "unconnected-(U6-D1-Pad16)") (class "Default")
      (node (ref "U6") (pin "16") (pinfunction "D1_16") (pintype "bidirectional"))
    )
    (net (code "191") (name "unconnected-(U6-D2-Pad17)") (class "Default")
      (node (ref "U6") (pin "17") (pinfunction "D2_17") (pintype "bidirectional"))
    )
    (net (code "192") (name "unconnected-(U6-D4-Pad19)") (class "Default")
      (node (ref "U6") (pin "19") (pinfunction "D4_19") (pintype "bidirectional"))
    )
    (net (code "193") (name "unconnected-(U6-D6-Pad21)") (class "Default")
      (node (ref "U6") (pin "21") (pinfunction "D6_21") (pintype "bidirectional"))
    )
    (net (code "194") (name "unconnected-(U6-INI#-Pad26)") (class "Default")
      (node (ref "U6") (pin "26") (pinfunction "INI#_26") (pintype "output"))
    )
    (net (code "195") (name "unconnected-(U6-SCL-Pad24)") (class "Default")
      (node (ref "U6") (pin "24") (pinfunction "SCL_24") (pintype "output"))
    )
    (net (code "196") (name "unconnected-(U6-SIN#-Pad3)") (class "Default")
      (node (ref "U6") (pin "3") (pinfunction "SIN#_3") (pintype "output"))
    )
    (net (code "197") (name "unconnected-(U6-SLCT-Pad8)") (class "Default")
      (node (ref "U6") (pin "8") (pinfunction "SLCT_8") (pintype "passive"))
    )
    (net (code "198") (name "unconnected-(U6-STB#-Pad25)") (class "Default")
      (node (ref "U6") (pin "25") (pinfunction "STB#_25") (pintype "output"))
    )
  )
)
